# Copy_of_STM32_F407_SchDoc.net
KiCad netlist of a schematic drawn in Altium Designer
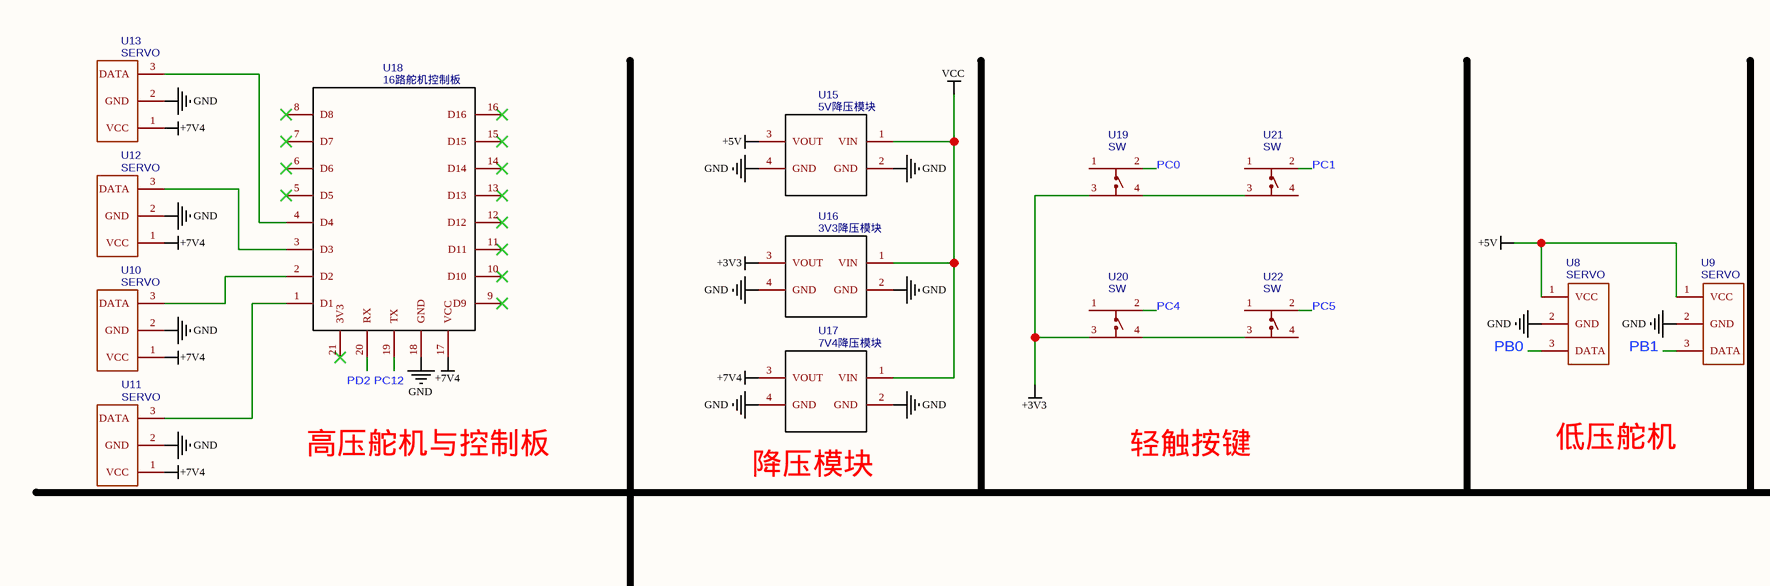
[diagram p0: Copy of STM32_F407.SchDoc.schdoc, top left]
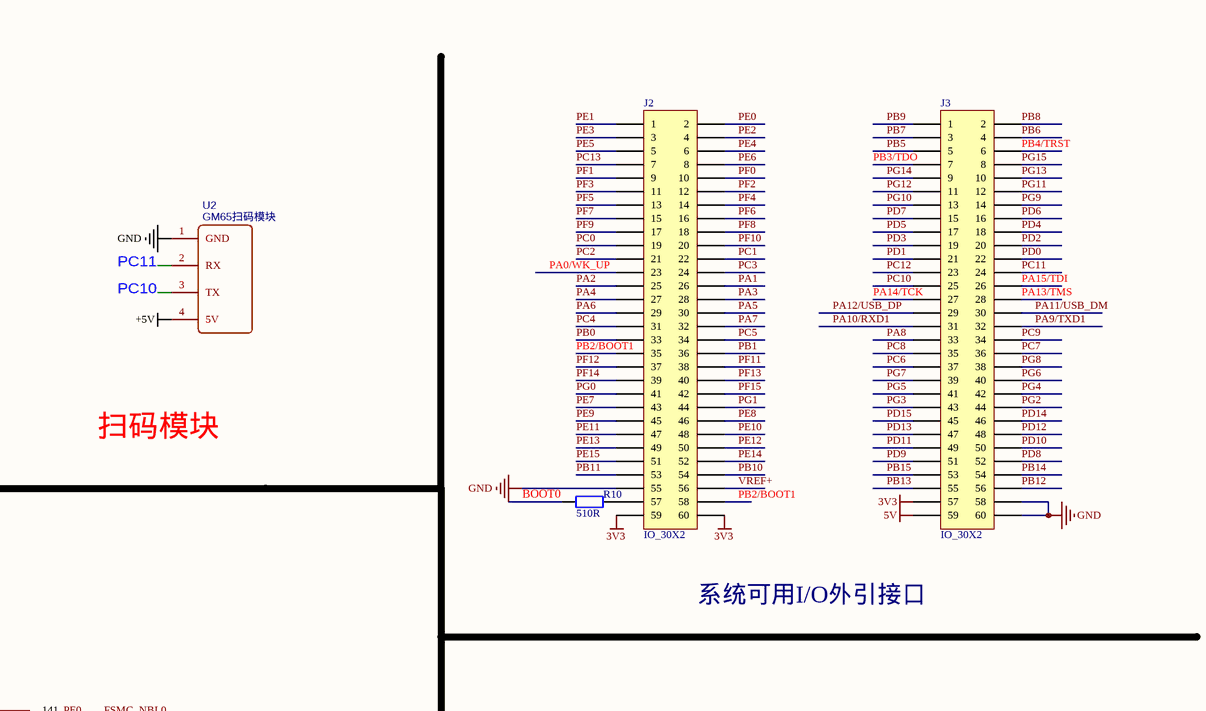
[diagram p1: Copy of STM32_F407.SchDoc.schdoc, top right]
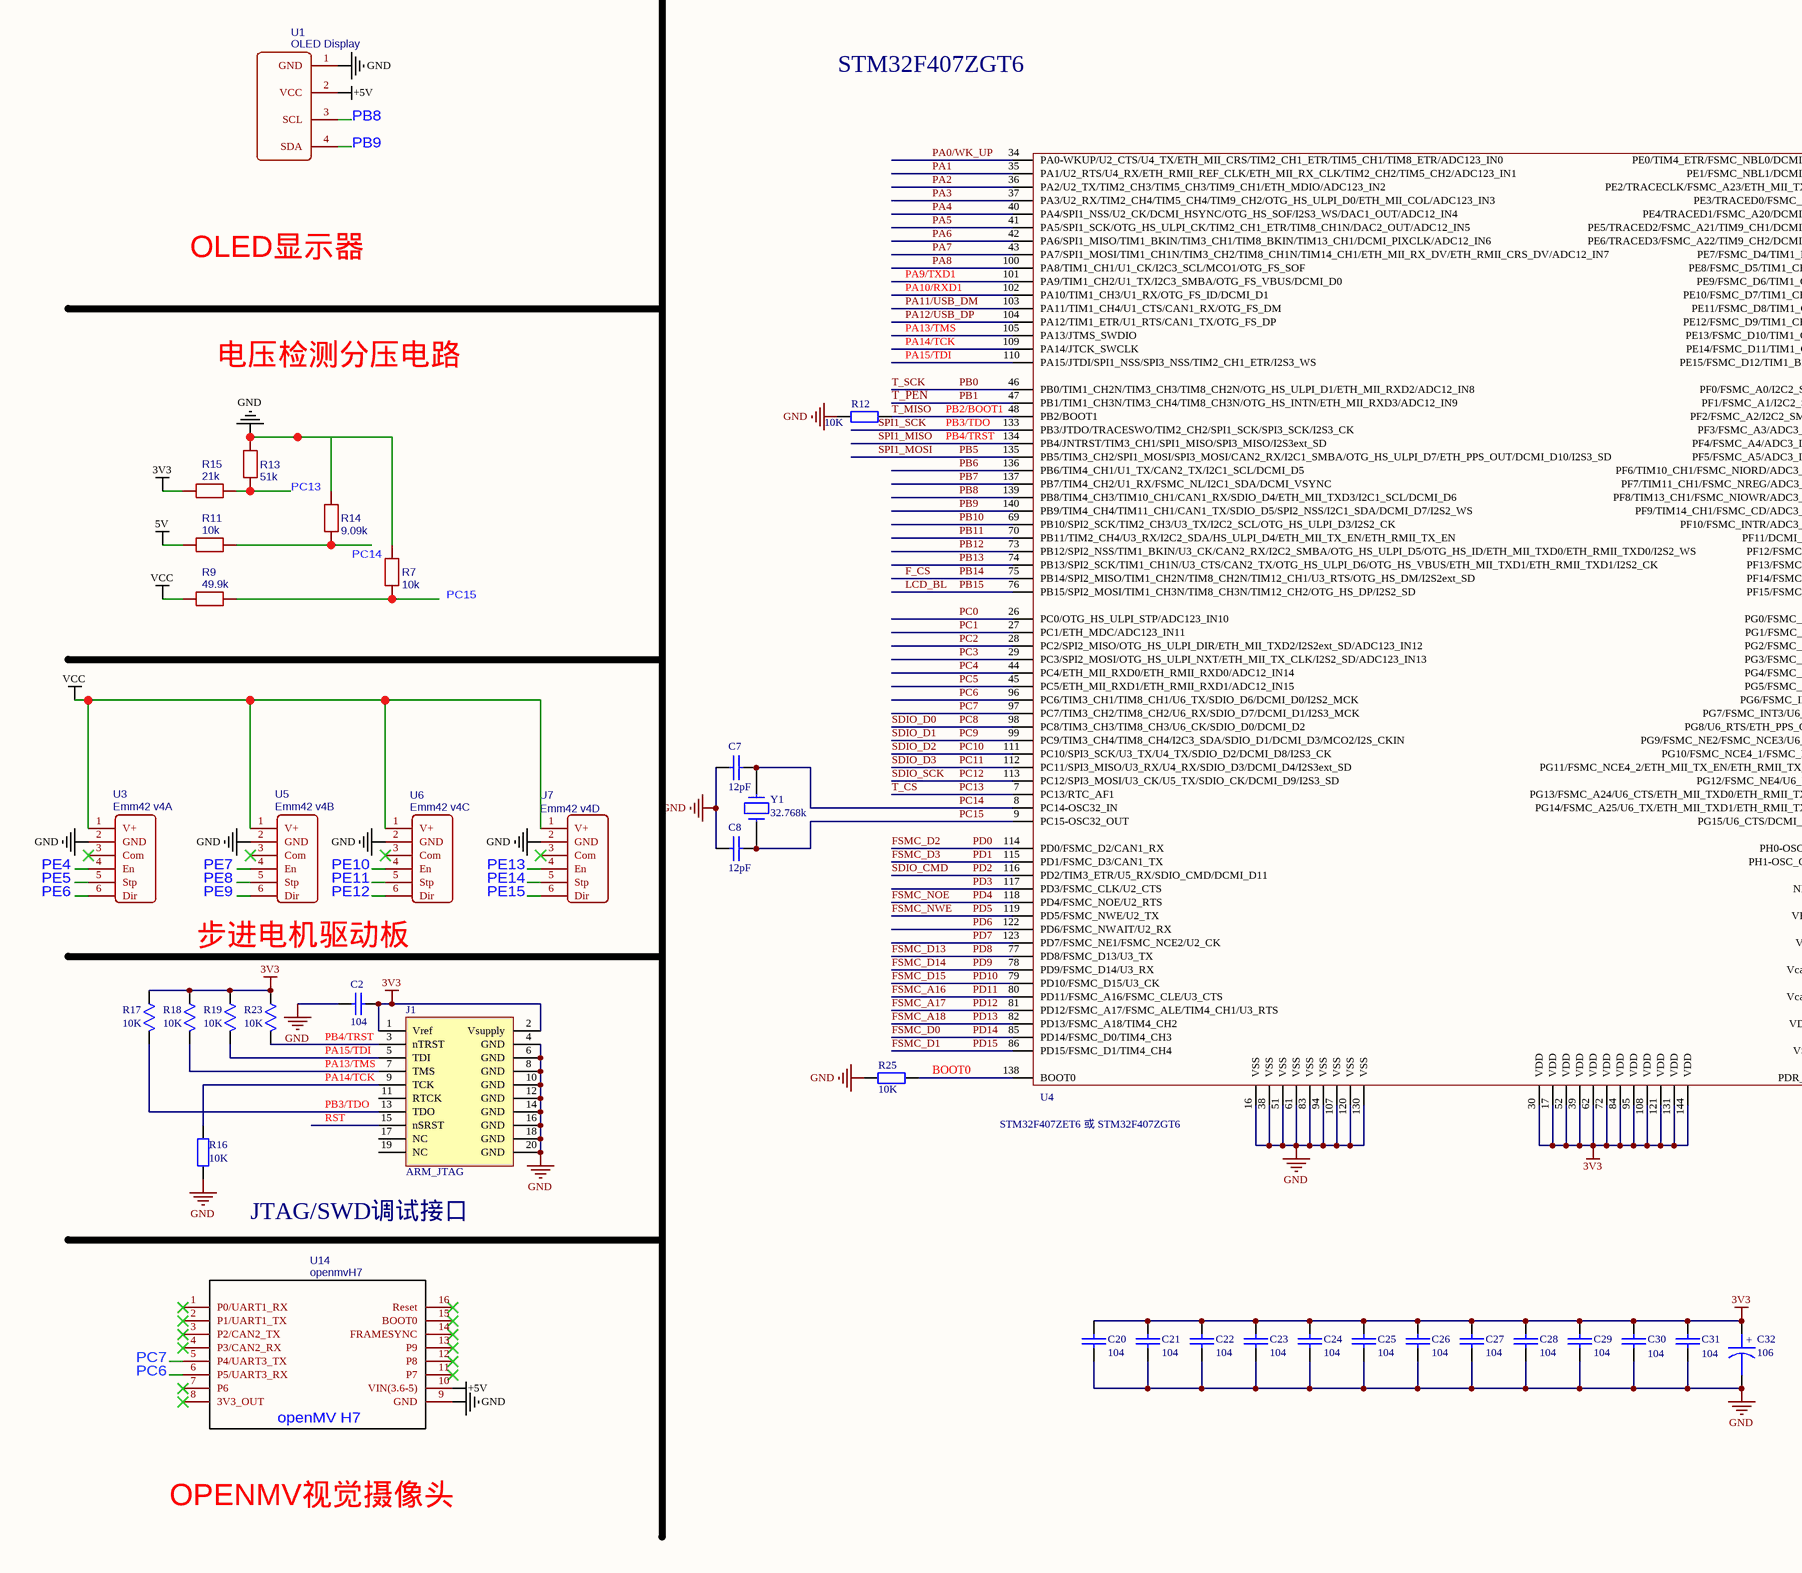
[diagram p2: Copy of STM32_F407.SchDoc.schdoc, bottom left]
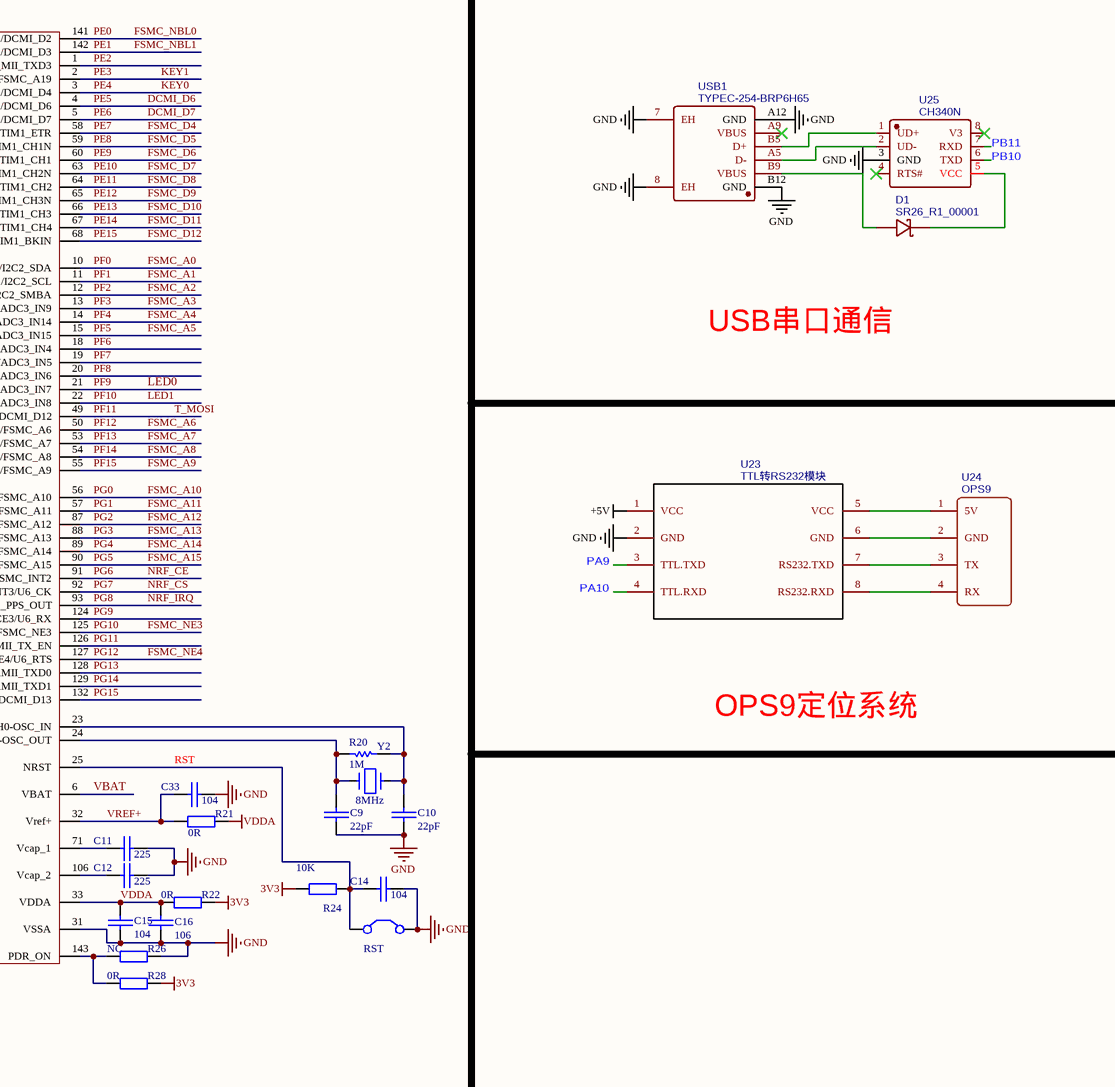
[diagram p3: Copy of STM32_F407.SchDoc.schdoc, bottom right]

(export (version "E")
  (design (tool "Eeschema 10.0.6"))
  (components
    (comp (ref "C2")
      (value "NO")
      (fields (field (name "PUBLISHER") "Altium Limited"))
      (libsource (lib "altium-import") (part "root_0_NO_"))
    )
    (comp (ref "C7") (value "12pF") (libsource (lib "altium-import") (part "root_1_12pF_")))
    (comp (ref "C8") (value "12pF") (libsource (lib "altium-import") (part "root_1_12pF_")))
    (comp (ref "C9") (value "22pF") (libsource (lib "altium-import") (part "root_0_22pF_")))
    (comp (ref "C10") (value "22pF") (libsource (lib "altium-import") (part "root_0_22pF_")))
    (comp (ref "C11") (value "225") (libsource (lib "altium-import") (part "root_1_225_")))
    (comp (ref "C12") (value "225") (libsource (lib "altium-import") (part "root_1_225_")))
    (comp (ref "C14") (value "104") (libsource (lib "") (part "root_1_104__1")))
    (comp (ref "C15") (value "104") (libsource (lib "altium-import") (part "root_2_104_")))
    (comp (ref "C16") (value "106") (libsource (lib "altium-import") (part "root_2_106_")))
    (comp (ref "C20") (value "104") (libsource (lib "altium-import") (part "root_0_104_")))
    (comp (ref "C21") (value "104") (libsource (lib "altium-import") (part "root_0_104_")))
    (comp (ref "C22") (value "104") (libsource (lib "altium-import") (part "root_0_104_")))
    (comp (ref "C23") (value "104") (libsource (lib "altium-import") (part "root_0_104_")))
    (comp (ref "C24") (value "104") (libsource (lib "altium-import") (part "root_0_104_")))
    (comp (ref "C25") (value "104") (libsource (lib "altium-import") (part "root_0_104_")))
    (comp (ref "C26") (value "104") (libsource (lib "altium-import") (part "root_0_104_")))
    (comp (ref "C27") (value "104") (libsource (lib "altium-import") (part "root_0_104_")))
    (comp (ref "C28") (value "104") (libsource (lib "altium-import") (part "root_0_104_")))
    (comp (ref "C29") (value "104") (libsource (lib "altium-import") (part "root_0_104_")))
    (comp (ref "C30") (value "104") (libsource (lib "altium-import") (part "root_0_104_")))
    (comp (ref "C31") (value "104") (libsource (lib "altium-import") (part "root_0_104_")))
    (comp (ref "C32") (value "106") (libsource (lib "altium-import") (part "root_0_106_")))
    (comp (ref "C33") (value "104") (libsource (lib "altium-import") (part "root_1_104_")))
    (comp (ref "D1")
      (value "SR26_R1_00001")
      (fields (field (name "MANUFACTURER") "PANJIT(强茂)") (field (name "CONTRIBUTOR") "LCSC"))
      (libsource (lib "altium-import") (part "root_2_SR26_R1_00001_"))
    )
    (comp (ref "J1") (value "ARM_JTAG") (libsource (lib "altium-import") (part "root_0_ARM_JTAG_")))
    (comp (ref "J2")
      (value "IO_30X2")
      (fields (field (name "PUBLISHER") "Altium Limited"))
      (libsource (lib "altium-import") (part "root_0_IO_30X2_"))
    )
    (comp (ref "J3")
      (value "IO_30X2")
      (fields (field (name "PUBLISHER") "Altium Limited"))
      (libsource (lib "altium-import") (part "root_0_IO_30X2_"))
    )
    (comp (ref "R7")
      (value "10k")
      (fields (field (name "CONTRIBUTOR") "LCEDA_Lib"))
      (libsource (lib "altium-import") (part "root_1_10k_"))
    )
    (comp (ref "R9")
      (value "49.9k")
      (fields (field (name "CONTRIBUTOR") "LCEDA_Lib"))
      (libsource (lib "altium-import") (part "root_0_49.9k_"))
    )
    (comp (ref "R10") (value "510R") (libsource (lib "altium-import") (part "root_2_510R_")))
    (comp (ref "R11")
      (value "10k")
      (fields (field (name "CONTRIBUTOR") "LCEDA_Lib"))
      (libsource (lib "altium-import") (part "root_0_10k_"))
    )
    (comp (ref "R12") (value "10K") (libsource (lib "altium-import") (part "root_2_10K_")))
    (comp (ref "R13")
      (value "51k")
      (fields (field (name "CONTRIBUTOR") "LCEDA_Lib"))
      (libsource (lib "altium-import") (part "root_1_51k_"))
    )
    (comp (ref "R14")
      (value "9.09k")
      (fields (field (name "CONTRIBUTOR") "LCEDA_Lib"))
      (libsource (lib "altium-import") (part "root_1_9.09k_"))
    )
    (comp (ref "R15")
      (value "21k")
      (fields (field (name "CONTRIBUTOR") "LCEDA_Lib"))
      (libsource (lib "altium-import") (part "root_0_21k_"))
    )
    (comp (ref "R16") (value "10K") (libsource (lib "altium-import") (part "root_1_10K_")))
    (comp (ref "R17") (value "10K") (libsource (lib "altium-import") (part "root_3_10K_")))
    (comp (ref "R18") (value "10K") (libsource (lib "altium-import") (part "root_3_10K_")))
    (comp (ref "R19") (value "10K") (libsource (lib "altium-import") (part "root_3_10K_")))
    (comp (ref "R20") (value "1M") (libsource (lib "altium-import") (part "root_0_1M_")))
    (comp (ref "R21") (value "0R") (libsource (lib "altium-import") (part "root_0_0R_")))
    (comp (ref "R22") (value "0R") (libsource (lib "altium-import") (part "root_0_0R_")))
    (comp (ref "R23") (value "10K") (libsource (lib "altium-import") (part "root_3_10K_")))
    (comp (ref "R24") (value "10K") (libsource (lib "altium-import") (part "root_2_10K_")))
    (comp (ref "R25") (value "10K") (libsource (lib "altium-import") (part "root_0_10K_")))
    (comp (ref "R26") (value "NC") (libsource (lib "altium-import") (part "root_0_NC_")))
    (comp (ref "R28") (value "0R") (libsource (lib "altium-import") (part "root_0_0R_")))
    (comp (ref "RST")
      (value "Key")
      (fields (field (name "PUBLISHER") "Altium Limited"))
      (libsource (lib "altium-import") (part "root_0_Key_"))
    )
    (comp (ref "U1")
      (value "OLED Display")
      (fields (field (name "CONTRIBUTOR") "mac149"))
      (libsource (lib "altium-import") (part "root_0_OLED Display_"))
    )
    (comp (ref "U2")
      (value "GM65扫码模块")
      (fields (field (name "CONTRIBUTOR") "mac149"))
      (libsource (lib "altium-import") (part "root_0_GM65扫码模块_"))
    )
    (comp (ref "U3")
      (value "Emm42 v4A")
      (fields (field (name "CONTRIBUTOR") "mac149"))
      (libsource (lib "altium-import") (part "root_0_Emm42 v4A_"))
    )
    (comp (ref "U4")
      (value "STM32F407ZET6 或 STM32F407ZGT6")
      (libsource (lib "altium-import") (part "root_0_STM32F407ZET6 或 STM32F407ZGT6_"))
    )
    (comp (ref "U5")
      (value "Emm42 v4B")
      (fields (field (name "CONTRIBUTOR") "mac149"))
      (libsource (lib "altium-import") (part "root_0_Emm42 v4B_"))
    )
    (comp (ref "U6")
      (value "Emm42 v4C")
      (fields (field (name "CONTRIBUTOR") "mac149"))
      (libsource (lib "altium-import") (part "root_0_Emm42 v4C_"))
    )
    (comp (ref "U7")
      (value "Emm42 v4D")
      (fields (field (name "CONTRIBUTOR") "mac149"))
      (libsource (lib "altium-import") (part "root_0_Emm42 v4D_"))
    )
    (comp (ref "U8")
      (value "SERVO")
      (fields (field (name "CONTRIBUTOR") "mac149"))
      (libsource (lib "altium-import") (part "root_0_SERVO_"))
    )
    (comp (ref "U9")
      (value "SERVO")
      (fields (field (name "CONTRIBUTOR") "mac149"))
      (libsource (lib "altium-import") (part "root_0_SERVO_"))
    )
    (comp (ref "U10")
      (value "SERVO")
      (fields (field (name "CONTRIBUTOR") "mac149"))
      (libsource (lib "altium-import") (part "root_2_SERVO_"))
    )
    (comp (ref "U11")
      (value "SERVO")
      (fields (field (name "CONTRIBUTOR") "mac149"))
      (libsource (lib "altium-import") (part "root_2_SERVO_"))
    )
    (comp (ref "U12")
      (value "SERVO")
      (fields (field (name "CONTRIBUTOR") "mac149"))
      (libsource (lib "altium-import") (part "root_2_SERVO_"))
    )
    (comp (ref "U13")
      (value "SERVO")
      (fields (field (name "CONTRIBUTOR") "mac149"))
      (libsource (lib "altium-import") (part "root_2_SERVO_"))
    )
    (comp (ref "U14")
      (value "openmvH7")
      (fields (field (name "CONTRIBUTOR") "xinb"))
      (libsource (lib "altium-import") (part "root_0_openmvH7_"))
    )
    (comp (ref "U15")
      (value "5V降压模块")
      (fields (field (name "CONTRIBUTOR") "mac149"))
      (libsource (lib "altium-import") (part "root_0_5V降压模块_"))
    )
    (comp (ref "U16")
      (value "3V3降压模块")
      (fields (field (name "CONTRIBUTOR") "mac149"))
      (libsource (lib "altium-import") (part "root_0_3V3降压模块_"))
    )
    (comp (ref "U17")
      (value "7V4降压模块")
      (fields (field (name "CONTRIBUTOR") "mac149"))
      (libsource (lib "altium-import") (part "root_0_7V4降压模块_"))
    )
    (comp (ref "U18")
      (value "16路舵机控制板")
      (fields (field (name "CONTRIBUTOR") "mac149"))
      (libsource (lib "altium-import") (part "root_2_16路舵机控制板_"))
    )
    (comp (ref "U19")
      (value "SW")
      (fields
        (field (name "MANUFACTURER") "DEALON(德艺隆)")
        (field (name "MANUFACTURER PART") "TD-1806SR-5.5H-250")
        (field (name "CONTRIBUTOR") "lcsc")
      )
      (libsource (lib "altium-import") (part "root_0_SW_"))
    )
    (comp (ref "U20")
      (value "SW")
      (fields
        (field (name "MANUFACTURER") "DEALON(德艺隆)")
        (field (name "MANUFACTURER PART") "TD-1806SR-5.5H-250")
        (field (name "CONTRIBUTOR") "lcsc")
      )
      (libsource (lib "altium-import") (part "root_0_SW_"))
    )
    (comp (ref "U21")
      (value "SW")
      (fields
        (field (name "MANUFACTURER") "DEALON(德艺隆)")
        (field (name "MANUFACTURER PART") "TD-1806SR-5.5H-250")
        (field (name "CONTRIBUTOR") "lcsc")
      )
      (libsource (lib "altium-import") (part "root_0_SW_"))
    )
    (comp (ref "U22")
      (value "SW")
      (fields
        (field (name "MANUFACTURER") "DEALON(德艺隆)")
        (field (name "MANUFACTURER PART") "TD-1806SR-5.5H-250")
        (field (name "CONTRIBUTOR") "lcsc")
      )
      (libsource (lib "altium-import") (part "root_0_SW_"))
    )
    (comp (ref "U23")
      (value "TTL转RS232模块")
      (fields (field (name "CONTRIBUTOR") "mac149"))
      (libsource (lib "altium-import") (part "root_0_TTL转RS232模块_"))
    )
    (comp (ref "U24")
      (value "OPS9")
      (fields (field (name "CONTRIBUTOR") "mac149"))
      (libsource (lib "altium-import") (part "root_0_OPS9_"))
    )
    (comp (ref "U25")
      (value "CH340N")
      (fields (field (name "MANUFACTURER") "WCH(南京沁恒)") (field (name "CONTRIBUTOR") "LCSC"))
      (libsource (lib "altium-import") (part "root_0_CH340N_"))
    )
    (comp (ref "USB1")
      (value "TYPEC-254-BRP6H65")
      (fields (field (name "MANUFACTURER") "XUNPU(讯普)") (field (name "CONTRIBUTOR") "LCSC"))
      (libsource (lib "altium-import") (part "root_2_TYPEC-254-BRP6H65_"))
    )
    (comp (ref "Y1") (value "8MHz") (libsource (lib "altium-import") (part "root_1_8MHz_")))
    (comp (ref "Y2") (value "8MHz") (libsource (lib "altium-import") (part "root_0_8MHz_")))
  )
  (nets
    (net (code "1") (name "+3V3") (class "Default")
      (node (ref "U16") (pin "3") (pinfunction "VOUT_3") (pintype "passive"))
      (node (ref "U19") (pin "3") (pinfunction "C_3") (pintype "passive"))
      (node (ref "U20") (pin "3") (pinfunction "C_3") (pintype "passive"))
    )
    (net (code "2") (name "+5V") (class "Default")
      (node (ref "U1") (pin "2") (pinfunction "VCC_2") (pintype "passive"))
      (node (ref "U14") (pin "10") (pinfunction "VIN(3.6-5)_10") (pintype "passive"))
      (node (ref "U15") (pin "3") (pinfunction "VOUT_3") (pintype "passive"))
      (node (ref "U2") (pin "4") (pinfunction "5V_4") (pintype "passive"))
      (node (ref "U23") (pin "1") (pinfunction "VCC_1") (pintype "passive"))
      (node (ref "U8") (pin "1") (pinfunction "VCC_1") (pintype "passive"))
      (node (ref "U9") (pin "1") (pinfunction "VCC_1") (pintype "passive"))
    )
    (net (code "3") (name "+7V4") (class "Default")
      (node (ref "U10") (pin "1") (pinfunction "VCC_1") (pintype "passive"))
      (node (ref "U11") (pin "1") (pinfunction "VCC_1") (pintype "passive"))
      (node (ref "U12") (pin "1") (pinfunction "VCC_1") (pintype "passive"))
      (node (ref "U13") (pin "1") (pinfunction "VCC_1") (pintype "passive"))
      (node (ref "U17") (pin "3") (pinfunction "VOUT_3") (pintype "passive"))
      (node (ref "U18") (pin "17") (pinfunction "VCC_17") (pintype "passive"))
    )
    (net (code "4") (name "/BOOT0") (class "Default")
      (node (ref "R10") (pin "2") (pinfunction "2_2") (pintype "passive"))
      (node (ref "R25") (pin "1") (pinfunction "1_1") (pintype "passive"))
      (node (ref "U4") (pin "138") (pinfunction "BOOT0_138") (pintype "passive"))
    )
    (net (code "5") (name "/DCMI_D6") (class "Default")
      (node (ref "J2") (pin "5") (pinfunction "5_5") (pintype "passive"))
      (node (ref "U4") (pin "4") (pinfunction "PE5/TRACED2/FSMC_A21/TIM9_CH1/DCMI_D6_4") (pintype "passive"))
    )
    (net (code "6") (name "/DCMI_D7") (class "Default")
      (node (ref "J2") (pin "8") (pinfunction "8_8") (pintype "passive"))
      (node (ref "U4") (pin "5") (pinfunction "PE6/TRACED3/FSMC_A22/TIM9_CH2/DCMI_D7_5") (pintype "passive"))
    )
    (net (code "7") (name "/FSMC_A0") (class "Default")
      (node (ref "J2") (pin "10") (pinfunction "10_10") (pintype "passive"))
      (node (ref "U4") (pin "10") (pinfunction "PF0/FSMC_A0/I2C2_SDA_10") (pintype "passive"))
    )
    (net (code "8") (name "/FSMC_A1") (class "Default")
      (node (ref "J2") (pin "9") (pinfunction "9_9") (pintype "passive"))
      (node (ref "U4") (pin "11") (pinfunction "PF1/FSMC_A1/I2C2_SCL_11") (pintype "passive"))
    )
    (net (code "9") (name "/FSMC_A2") (class "Default")
      (node (ref "J2") (pin "12") (pinfunction "12_12") (pintype "passive"))
      (node (ref "U4") (pin "12") (pinfunction "PF2/FSMC_A2/I2C2_SMBA_12") (pintype "passive"))
    )
    (net (code "10") (name "/FSMC_A3") (class "Default")
      (node (ref "J2") (pin "11") (pinfunction "11_11") (pintype "passive"))
      (node (ref "U4") (pin "13") (pinfunction "PF3/FSMC_A3/ADC3_IN9_13") (pintype "passive"))
    )
    (net (code "11") (name "/FSMC_A4") (class "Default")
      (node (ref "J2") (pin "14") (pinfunction "14_14") (pintype "passive"))
      (node (ref "U4") (pin "14") (pinfunction "PF4/FSMC_A4/ADC3_IN14_14") (pintype "passive"))
    )
    (net (code "12") (name "/FSMC_A5") (class "Default")
      (node (ref "J2") (pin "13") (pinfunction "13_13") (pintype "passive"))
      (node (ref "U4") (pin "15") (pinfunction "PF5/FSMC_A5/ADC3_IN15_15") (pintype "passive"))
    )
    (net (code "13") (name "/FSMC_A6") (class "Default")
      (node (ref "J2") (pin "37") (pinfunction "37_37") (pintype "passive"))
      (node (ref "U4") (pin "50") (pinfunction "PF12/FSMC_A6_50") (pintype "passive"))
    )
    (net (code "14") (name "/FSMC_A7") (class "Default")
      (node (ref "J2") (pin "40") (pinfunction "40_40") (pintype "passive"))
      (node (ref "U4") (pin "53") (pinfunction "PF13/FSMC_A7_53") (pintype "passive"))
    )
    (net (code "15") (name "/FSMC_A8") (class "Default")
      (node (ref "J2") (pin "39") (pinfunction "39_39") (pintype "passive"))
      (node (ref "U4") (pin "54") (pinfunction "PF14/FSMC_A8_54") (pintype "passive"))
    )
    (net (code "16") (name "/FSMC_A9") (class "Default")
      (node (ref "J2") (pin "42") (pinfunction "42_42") (pintype "passive"))
      (node (ref "U4") (pin "55") (pinfunction "PF15/FSMC_A9_55") (pintype "passive"))
    )
    (net (code "17") (name "/FSMC_A10") (class "Default")
      (node (ref "J2") (pin "41") (pinfunction "41_41") (pintype "passive"))
      (node (ref "U4") (pin "56") (pinfunction "PG0/FSMC_A10_56") (pintype "passive"))
    )
    (net (code "18") (name "/FSMC_A11") (class "Default")
      (node (ref "J2") (pin "44") (pinfunction "44_44") (pintype "passive"))
      (node (ref "U4") (pin "57") (pinfunction "PG1/FSMC_A11_57") (pintype "passive"))
    )
    (net (code "19") (name "/FSMC_A12") (class "Default")
      (node (ref "J3") (pin "44") (pinfunction "44_44") (pintype "passive"))
      (node (ref "U4") (pin "87") (pinfunction "PG2/FSMC_A12_87") (pintype "passive"))
    )
    (net (code "20") (name "/FSMC_A13") (class "Default")
      (node (ref "J3") (pin "43") (pinfunction "43_43") (pintype "passive"))
      (node (ref "U4") (pin "88") (pinfunction "PG3/FSMC_A13_88") (pintype "passive"))
    )
    (net (code "21") (name "/FSMC_A14") (class "Default")
      (node (ref "J3") (pin "42") (pinfunction "42_42") (pintype "passive"))
      (node (ref "U4") (pin "89") (pinfunction "PG4/FSMC_A14_89") (pintype "passive"))
    )
    (net (code "22") (name "/FSMC_A15") (class "Default")
      (node (ref "J3") (pin "41") (pinfunction "41_41") (pintype "passive"))
      (node (ref "U4") (pin "90") (pinfunction "PG5/FSMC_A15_90") (pintype "passive"))
    )
    (net (code "23") (name "/FSMC_A16") (class "Default")
      (node (ref "J3") (pin "49") (pinfunction "49_49") (pintype "passive"))
      (node (ref "U4") (pin "80") (pinfunction "PD11/FSMC_A16/FSMC_CLE/U3_CTS_80") (pintype "passive"))
    )
    (net (code "24") (name "/FSMC_A17") (class "Default")
      (node (ref "J3") (pin "48") (pinfunction "48_48") (pintype "passive"))
      (node (ref "U4") (pin "81") (pinfunction "PD12/FSMC_A17/FSMC_ALE/TIM4_CH1/U3_RTS_81") (pintype "passive"))
    )
    (net (code "25") (name "/FSMC_A18") (class "Default")
      (node (ref "J3") (pin "47") (pinfunction "47_47") (pintype "passive"))
      (node (ref "U4") (pin "82") (pinfunction "PD13/FSMC_A18/TIM4_CH2_82") (pintype "passive"))
    )
    (net (code "26") (name "/FSMC_D0") (class "Default")
      (node (ref "J3") (pin "46") (pinfunction "46_46") (pintype "passive"))
      (node (ref "U4") (pin "85") (pinfunction "PD14/FSMC_D0/TIM4_CH3_85") (pintype "passive"))
    )
    (net (code "27") (name "/FSMC_D1") (class "Default")
      (node (ref "J3") (pin "45") (pinfunction "45_45") (pintype "passive"))
      (node (ref "U4") (pin "86") (pinfunction "PD15/FSMC_D1/TIM4_CH4_86") (pintype "passive"))
    )
    (net (code "28") (name "/FSMC_D2") (class "Default")
      (node (ref "J3") (pin "22") (pinfunction "22_22") (pintype "passive"))
      (node (ref "U4") (pin "114") (pinfunction "PD0/FSMC_D2/CAN1_RX_114") (pintype "passive"))
    )
    (net (code "29") (name "/FSMC_D3") (class "Default")
      (node (ref "J3") (pin "21") (pinfunction "21_21") (pintype "passive"))
      (node (ref "U4") (pin "115") (pinfunction "PD1/FSMC_D3/CAN1_TX_115") (pintype "passive"))
    )
    (net (code "30") (name "/FSMC_D4") (class "Default")
      (node (ref "J2") (pin "43") (pinfunction "43_43") (pintype "passive"))
      (node (ref "U4") (pin "58") (pinfunction "PE7/FSMC_D4/TIM1_ETR_58") (pintype "passive"))
    )
    (net (code "31") (name "/FSMC_D5") (class "Default")
      (node (ref "J2") (pin "46") (pinfunction "46_46") (pintype "passive"))
      (node (ref "U4") (pin "59") (pinfunction "PE8/FSMC_D5/TIM1_CH1N_59") (pintype "passive"))
    )
    (net (code "32") (name "/FSMC_D6") (class "Default")
      (node (ref "J2") (pin "45") (pinfunction "45_45") (pintype "passive"))
      (node (ref "U4") (pin "60") (pinfunction "PE9/FSMC_D6/TIM1_CH1_60") (pintype "passive"))
    )
    (net (code "33") (name "/FSMC_D7") (class "Default")
      (node (ref "J2") (pin "48") (pinfunction "48_48") (pintype "passive"))
      (node (ref "U4") (pin "63") (pinfunction "PE10/FSMC_D7/TIM1_CH2N_63") (pintype "passive"))
    )
    (net (code "34") (name "/FSMC_D8") (class "Default")
      (node (ref "J2") (pin "47") (pinfunction "47_47") (pintype "passive"))
      (node (ref "U4") (pin "64") (pinfunction "PE11/FSMC_D8/TIM1_CH2_64") (pintype "passive"))
    )
    (net (code "35") (name "/FSMC_D9") (class "Default")
      (node (ref "J2") (pin "50") (pinfunction "50_50") (pintype "passive"))
      (node (ref "U4") (pin "65") (pinfunction "PE12/FSMC_D9/TIM1_CH3N_65") (pintype "passive"))
    )
    (net (code "36") (name "/FSMC_D10") (class "Default")
      (node (ref "J2") (pin "49") (pinfunction "49_49") (pintype "passive"))
      (node (ref "U4") (pin "66") (pinfunction "PE13/FSMC_D10/TIM1_CH3_66") (pintype "passive"))
    )
    (net (code "37") (name "/FSMC_D11") (class "Default")
      (node (ref "J2") (pin "52") (pinfunction "52_52") (pintype "passive"))
      (node (ref "U4") (pin "67") (pinfunction "PE14/FSMC_D11/TIM1_CH4_67") (pintype "passive"))
    )
    (net (code "38") (name "/FSMC_D12") (class "Default")
      (node (ref "J2") (pin "51") (pinfunction "51_51") (pintype "passive"))
      (node (ref "U4") (pin "68") (pinfunction "PE15/FSMC_D12/TIM1_BKIN_68") (pintype "passive"))
    )
    (net (code "39") (name "/FSMC_D13") (class "Default")
      (node (ref "J3") (pin "52") (pinfunction "52_52") (pintype "passive"))
      (node (ref "U4") (pin "77") (pinfunction "PD8/FSMC_D13/U3_TX_77") (pintype "passive"))
    )
    (net (code "40") (name "/FSMC_D14") (class "Default")
      (node (ref "J3") (pin "51") (pinfunction "51_51") (pintype "passive"))
      (node (ref "U4") (pin "78") (pinfunction "PD9/FSMC_D14/U3_RX_78") (pintype "passive"))
    )
    (net (code "41") (name "/FSMC_D15") (class "Default")
      (node (ref "J3") (pin "50") (pinfunction "50_50") (pintype "passive"))
      (node (ref "U4") (pin "79") (pinfunction "PD10/FSMC_D15/U3_CK_79") (pintype "passive"))
    )
    (net (code "42") (name "/FSMC_NBL0") (class "Default")
      (node (ref "J2") (pin "2") (pinfunction "2_2") (pintype "passive"))
      (node (ref "U4") (pin "141") (pinfunction "PE0/TIM4_ETR/FSMC_NBL0/DCMI_D2_141") (pintype "passive"))
    )
    (net (code "43") (name "/FSMC_NBL1") (class "Default")
      (node (ref "J2") (pin "1") (pinfunction "1_1") (pintype "passive"))
      (node (ref "U4") (pin "142") (pinfunction "PE1/FSMC_NBL1/DCMI_D3_142") (pintype "passive"))
    )
    (net (code "44") (name "/FSMC_NE3") (class "Default")
      (node (ref "J3") (pin "13") (pinfunction "13_13") (pintype "passive"))
      (node (ref "U4") (pin "125") (pinfunction "PG10/FSMC_NCE4_1/FSMC_NE3_125") (pintype "passive"))
    )
    (net (code "45") (name "/FSMC_NE4") (class "Default")
      (node (ref "J3") (pin "11") (pinfunction "11_11") (pintype "passive"))
      (node (ref "U4") (pin "127") (pinfunction "PG12/FSMC_NE4/U6_RTS_127") (pintype "passive"))
    )
    (net (code "46") (name "/FSMC_NOE") (class "Default")
      (node (ref "J3") (pin "18") (pinfunction "18_18") (pintype "passive"))
      (node (ref "U4") (pin "118") (pinfunction "PD4/FSMC_NOE/U2_RTS_118") (pintype "passive"))
    )
    (net (code "47") (name "/FSMC_NWE") (class "Default")
      (node (ref "J3") (pin "17") (pinfunction "17_17") (pintype "passive"))
      (node (ref "U4") (pin "119") (pinfunction "PD5/FSMC_NWE/U2_TX_119") (pintype "passive"))
    )
    (net (code "48") (name "/F_CS") (class "Default")
      (node (ref "J3") (pin "54") (pinfunction "54_54") (pintype "passive"))
      (node (ref "U4") (pin "75") (pinfunction "PB14/SPI2_MISO/TIM1_CH2N/TIM8_CH2N/TIM12_CH1/U3_RTS/OTG_HS_DM/I2S2ext_SD_75") (pintype "passive"))
    )
    (net (code "49") (name "/KEY0") (class "Default")
      (node (ref "J2") (pin "6") (pinfunction "6_6") (pintype "passive"))
      (node (ref "U4") (pin "3") (pinfunction "PE4/TRACED1/FSMC_A20/DCMI_D4_3") (pintype "passive"))
    )
    (net (code "50") (name "/KEY1") (class "Default")
      (node (ref "J2") (pin "3") (pinfunction "3_3") (pintype "passive"))
      (node (ref "U4") (pin "2") (pinfunction "PE3/TRACED0/FSMC_A19_2") (pintype "passive"))
    )
    (net (code "51") (name "/LCD_BL") (class "Default")
      (node (ref "J3") (pin "53") (pinfunction "53_53") (pintype "passive"))
      (node (ref "U4") (pin "76") (pinfunction "PB15/SPI2_MOSI/TIM1_CH3N/TIM8_CH3N/TIM12_CH2/OTG_HS_DP/I2S2_SD_76") (pintype "passive"))
    )
    (net (code "52") (name "/LED0") (class "Default")
      (node (ref "J2") (pin "17") (pinfunction "17_17") (pintype "passive"))
      (node (ref "U4") (pin "21") (pinfunction "PF9/TIM14_CH1/FSMC_CD/ADC3_IN7_21") (pintype "passive"))
    )
    (net (code "53") (name "/LED1") (class "Default")
      (node (ref "J2") (pin "20") (pinfunction "20_20") (pintype "passive"))
      (node (ref "U4") (pin "22") (pinfunction "PF10/FSMC_INTR/ADC3_IN8_22") (pintype "passive"))
    )
    (net (code "54") (name "/NRF_CE") (class "Default")
      (node (ref "J3") (pin "40") (pinfunction "40_40") (pintype "passive"))
      (node (ref "U4") (pin "91") (pinfunction "PG6/FSMC_INT2_91") (pintype "passive"))
    )
    (net (code "55") (name "/NRF_CS") (class "Default")
      (node (ref "J3") (pin "39") (pinfunction "39_39") (pintype "passive"))
      (node (ref "U4") (pin "92") (pinfunction "PG7/FSMC_INT3/U6_CK_92") (pintype "passive"))
    )
    (net (code "56") (name "/NRF_IRQ") (class "Default")
      (node (ref "J3") (pin "38") (pinfunction "38_38") (pintype "passive"))
      (node (ref "U4") (pin "93") (pinfunction "PG8/U6_RTS/ETH_PPS_OUT_93") (pintype "passive"))
    )
    (net (code "57") (name "/PA0{slash}WK_UP") (class "Default")
      (node (ref "J2") (pin "23") (pinfunction "23_23") (pintype "passive"))
      (node (ref "U4") (pin "34") (pinfunction "PA0-WKUP/U2_CTS/U4_TX/ETH_MII_CRS/TIM2_CH1_ETR/TIM5_CH1/TIM8_ETR/ADC123_IN0_34") (pintype "passive"))
    )
    (net (code "58") (name "/PA1") (class "Default")
      (node (ref "J2") (pin "26") (pinfunction "26_26") (pintype "passive"))
      (node (ref "U4") (pin "35") (pinfunction "PA1/U2_RTS/U4_RX/ETH_RMII_REF_CLK/ETH_MII_RX_CLK/TIM2_CH2/TIM5_CH2/ADC123_IN1_35") (pintype "passive"))
    )
    (net (code "59") (name "/PA2") (class "Default")
      (node (ref "J2") (pin "25") (pinfunction "25_25") (pintype "passive"))
      (node (ref "U4") (pin "36") (pinfunction "PA2/U2_TX/TIM2_CH3/TIM5_CH3/TIM9_CH1/ETH_MDIO/ADC123_IN2_36") (pintype "passive"))
    )
    (net (code "60") (name "/PA3") (class "Default")
      (node (ref "J2") (pin "28") (pinfunction "28_28") (pintype "passive"))
      (node (ref "U4") (pin "37") (pinfunction "PA3/U2_RX/TIM2_CH4/TIM5_CH4/TIM9_CH2/OTG_HS_ULPI_D0/ETH_MII_COL/ADC123_IN3_37") (pintype "passive"))
    )
    (net (code "61") (name "/PA4") (class "Default")
      (node (ref "J2") (pin "27") (pinfunction "27_27") (pintype "passive"))
      (node (ref "U4") (pin "40") (pinfunction "PA4/SPI1_NSS/U2_CK/DCMI_HSYNC/OTG_HS_SOF/I2S3_WS/DAC1_OUT/ADC12_IN4_40") (pintype "passive"))
    )
    (net (code "62") (name "/PA5") (class "Default")
      (node (ref "J2") (pin "30") (pinfunction "30_30") (pintype "passive"))
      (node (ref "U4") (pin "41") (pinfunction "PA5/SPI1_SCK/OTG_HS_ULPI_CK/TIM2_CH1_ETR/TIM8_CH1N/DAC2_OUT/ADC12_IN5_41") (pintype "passive"))
    )
    (net (code "63") (name "/PA6") (class "Default")
      (node (ref "J2") (pin "29") (pinfunction "29_29") (pintype "passive"))
      (node (ref "U4") (pin "42") (pinfunction "PA6/SPI1_MISO/TIM1_BKIN/TIM3_CH1/TIM8_BKIN/TIM13_CH1/DCMI_PIXCLK/ADC12_IN6_42") (pintype "passive"))
    )
    (net (code "64") (name "/PA7") (class "Default")
      (node (ref "J2") (pin "32") (pinfunction "32_32") (pintype "passive"))
      (node (ref "U4") (pin "43") (pinfunction "PA7/SPI1_MOSI/TIM1_CH1N/TIM3_CH2/TIM8_CH1N/TIM14_CH1/ETH_MII_RX_DV/ETH_RMII_CRS_DV/ADC12_IN7_43") (pintype "passive"))
    )
    (net (code "65") (name "/PA8") (class "Default")
      (node (ref "J3") (pin "33") (pinfunction "33_33") (pintype "passive"))
      (node (ref "U4") (pin "100") (pinfunction "PA8/TIM1_CH1/U1_CK/I2C3_SCL/MCO1/OTG_FS_SOF_100") (pintype "passive"))
    )
    (net (code "66") (name "/PA9{slash}TXD1") (class "Default")
      (node (ref "J3") (pin "32") (pinfunction "32_32") (pintype "passive"))
      (node (ref "U4") (pin "101") (pinfunction "PA9/TIM1_CH2/U1_TX/I2C3_SMBA/OTG_FS_VBUS/DCMI_D0_101") (pintype "passive"))
    )
    (net (code "67") (name "/PA10{slash}RXD1") (class "Default")
      (node (ref "J3") (pin "31") (pinfunction "31_31") (pintype "passive"))
      (node (ref "U4") (pin "102") (pinfunction "PA10/TIM1_CH3/U1_RX/OTG_FS_ID/DCMI_D1_102") (pintype "passive"))
    )
    (net (code "68") (name "/PA11{slash}USB_DM") (class "Default")
      (node (ref "J3") (pin "30") (pinfunction "30_30") (pintype "passive"))
      (node (ref "U4") (pin "103") (pinfunction "PA11/TIM1_CH4/U1_CTS/CAN1_RX/OTG_FS_DM_103") (pintype "passive"))
    )
    (net (code "69") (name "/PA12{slash}USB_DP") (class "Default")
      (node (ref "J3") (pin "29") (pinfunction "29_29") (pintype "passive"))
      (node (ref "U4") (pin "104") (pinfunction "PA12/TIM1_ETR/U1_RTS/CAN1_TX/OTG_FS_DP_104") (pintype "passive"))
    )
    (net (code "70") (name "/PA13{slash}TMS") (class "Default")
      (node (ref "J1") (pin "7") (pinfunction "TMS_7") (pintype "passive"))
      (node (ref "J3") (pin "28") (pinfunction "28_28") (pintype "passive"))
      (node (ref "R18") (pin "2") (pinfunction "2_2") (pintype "passive"))
      (node (ref "U4") (pin "105") (pinfunction "PA13/JTMS_SWDIO_105") (pintype "passive"))
    )
    (net (code "71") (name "/PA14{slash}TCK") (class "Default")
      (node (ref "J1") (pin "9") (pinfunction "TCK_9") (pintype "passive"))
      (node (ref "J3") (pin "27") (pinfunction "27_27") (pintype "passive"))
      (node (ref "R16") (pin "2") (pinfunction "2_2") (pintype "passive"))
      (node (ref "U4") (pin "109") (pinfunction "PA14/JTCK_SWCLK_109") (pintype "passive"))
    )
    (net (code "72") (name "/PA15{slash}TDI") (class "Default")
      (node (ref "J1") (pin "5") (pinfunction "TDI_5") (pintype "passive"))
      (node (ref "J3") (pin "26") (pinfunction "26_26") (pintype "passive"))
      (node (ref "R19") (pin "2") (pinfunction "2_2") (pintype "passive"))
      (node (ref "U4") (pin "110") (pinfunction "PA15/JTDI/SPI1_NSS/SPI3_NSS/TIM2_CH1_ETR/I2S3_WS_110") (pintype "passive"))
    )
    (net (code "73") (name "/PB0") (class "Default")
      (node (ref "J2") (pin "33") (pinfunction "33_33") (pintype "passive"))
      (node (ref "U4") (pin "46") (pinfunction "PB0/TIM1_CH2N/TIM3_CH3/TIM8_CH2N/OTG_HS_ULPI_D1/ETH_MII_RXD2/ADC12_IN8_46") (pintype "passive"))
    )
    (net (code "74") (name "/PB1") (class "Default")
      (node (ref "J2") (pin "36") (pinfunction "36_36") (pintype "passive"))
      (node (ref "U4") (pin "47") (pinfunction "PB1/TIM1_CH3N/TIM3_CH4/TIM8_CH3N/OTG_HS_INTN/ETH_MII_RXD3/ADC12_IN9_47") (pintype "passive"))
    )
    (net (code "75") (name "/PB2{slash}BOOT1") (class "Default")
      (node (ref "J2") (pin "35") (pinfunction "35_35") (pintype "passive"))
      (node (ref "J2") (pin "58") (pinfunction "58_58") (pintype "passive"))
      (node (ref "R12") (pin "1") (pinfunction "1_1") (pintype "passive"))
      (node (ref "U4") (pin "48") (pinfunction "PB2/BOOT1_48") (pintype "passive"))
    )
    (net (code "76") (name "/PB3{slash}TDO") (class "Default")
      (node (ref "J1") (pin "13") (pinfunction "TDO_13") (pintype "passive"))
      (node (ref "J3") (pin "7") (pinfunction "7_7") (pintype "passive"))
      (node (ref "R17") (pin "2") (pinfunction "2_2") (pintype "passive"))
      (node (ref "U4") (pin "133") (pinfunction "PB3/JTDO/TRACESWO/TIM2_CH2/SPI1_SCK/SPI3_SCK/I2S3_CK_133") (pintype "passive"))
    )
    (net (code "77") (name "/PB4{slash}TRST") (class "Default")
      (node (ref "J1") (pin "3") (pinfunction "nTRST_3") (pintype "passive"))
      (node (ref "J3") (pin "6") (pinfunction "6_6") (pintype "passive"))
      (node (ref "R23") (pin "2") (pinfunction "2_2") (pintype "passive"))
      (node (ref "U4") (pin "134") (pinfunction "PB4/JNTRST/TIM3_CH1/SPI1_MISO/SPI3_MISO/I2S3ext_SD_134") (pintype "passive"))
    )
    (net (code "78") (name "/PB5") (class "Default")
      (node (ref "J3") (pin "5") (pinfunction "5_5") (pintype "passive"))
      (node (ref "U4") (pin "135") (pinfunction "PB5/TIM3_CH2/SPI1_MOSI/SPI3_MOSI/CAN2_RX/I2C1_SMBA/OTG_HS_ULPI_D7/ETH_PPS_OUT/DCMI_D10/I2S3_SD_135") (pintype "passive"))
    )
    (net (code "79") (name "/PB6") (class "Default")
      (node (ref "J3") (pin "4") (pinfunction "4_4") (pintype "passive"))
      (node (ref "U4") (pin "136") (pinfunction "PB6/TIM4_CH1/U1_TX/CAN2_TX/I2C1_SCL/DCMI_D5_136") (pintype "passive"))
    )
    (net (code "80") (name "/PB7") (class "Default")
      (node (ref "J3") (pin "3") (pinfunction "3_3") (pintype "passive"))
      (node (ref "U4") (pin "137") (pinfunction "PB7/TIM4_CH2/U1_RX/FSMC_NL/I2C1_SDA/DCMI_VSYNC_137") (pintype "passive"))
    )
    (net (code "81") (name "/PB8") (class "Default")
      (node (ref "J3") (pin "2") (pinfunction "2_2") (pintype "passive"))
      (node (ref "U4") (pin "139") (pinfunction "PB8/TIM4_CH3/TIM10_CH1/CAN1_RX/SDIO_D4/ETH_MII_TXD3/I2C1_SCL/DCMI_D6_139") (pintype "passive"))
    )
    (net (code "82") (name "/PB9") (class "Default")
      (node (ref "J3") (pin "1") (pinfunction "1_1") (pintype "passive"))
      (node (ref "U4") (pin "140") (pinfunction "PB9/TIM4_CH4/TIM11_CH1/CAN1_TX/SDIO_D5/SPI2_NSS/I2C1_SDA/DCMI_D7/I2S2_WS_140") (pintype "passive"))
    )
    (net (code "83") (name "/PB10") (class "Default")
      (node (ref "J2") (pin "54") (pinfunction "54_54") (pintype "passive"))
      (node (ref "U4") (pin "69") (pinfunction "PB10/SPI2_SCK/TIM2_CH3/U3_TX/I2C2_SCL/OTG_HS_ULPI_D3/I2S2_CK_69") (pintype "passive"))
    )
    (net (code "84") (name "/PB11") (class "Default")
      (node (ref "J2") (pin "53") (pinfunction "53_53") (pintype "passive"))
      (node (ref "U4") (pin "70") (pinfunction "PB11/TIM2_CH4/U3_RX/I2C2_SDA/HS_ULPI_D4/ETH_MII_TX_EN/ETH_RMII_TX_EN_70") (pintype "passive"))
    )
    (net (code "85") (name "/PB12") (class "Default")
      (node (ref "J3") (pin "56") (pinfunction "56_56") (pintype "passive"))
      (node (ref "U4") (pin "73") (pinfunction "PB12/SPI2_NSS/TIM1_BKIN/U3_CK/CAN2_RX/I2C2_SMBA/OTG_HS_ULPI_D5/OTG_HS_ID/ETH_MII_TXD0/ETH_RMII_TXD0/I2S2_WS_73") (pintype "passive"))
    )
    (net (code "86") (name "/PB13") (class "Default")
      (node (ref "J3") (pin "55") (pinfunction "55_55") (pintype "passive"))
      (node (ref "U4") (pin "74") (pinfunction "PB13/SPI2_SCK/TIM1_CH1N/U3_CTS/CAN2_TX/OTG_HS_ULPI_D6/OTG_HS_VBUS/ETH_MII_TXD1/ETH_RMII_TXD1/I2S2_CK_74") (pintype "passive"))
    )
    (net (code "87") (name "/PC0") (class "Default")
      (node (ref "J2") (pin "19") (pinfunction "19_19") (pintype "passive"))
      (node (ref "U4") (pin "26") (pinfunction "PC0/OTG_HS_ULPI_STP/ADC123_IN10_26") (pintype "passive"))
    )
    (net (code "88") (name "/PC1") (class "Default")
      (node (ref "J2") (pin "22") (pinfunction "22_22") (pintype "passive"))
      (node (ref "U4") (pin "27") (pinfunction "PC1/ETH_MDC/ADC123_IN11_27") (pintype "passive"))
    )
    (net (code "89") (name "/PC2") (class "Default")
      (node (ref "J2") (pin "21") (pinfunction "21_21") (pintype "passive"))
      (node (ref "U4") (pin "28") (pinfunction "PC2/SPI2_MISO/OTG_HS_ULPI_DIR/ETH_MII_TXD2/I2S2ext_SD/ADC123_IN12_28") (pintype "passive"))
    )
    (net (code "90") (name "/PC3") (class "Default")
      (node (ref "J2") (pin "24") (pinfunction "24_24") (pintype "passive"))
      (node (ref "U4") (pin "29") (pinfunction "PC3/SPI2_MOSI/OTG_HS_ULPI_NXT/ETH_MII_TX_CLK/I2S2_SD/ADC123_IN13_29") (pintype "passive"))
    )
    (net (code "91") (name "/PC4") (class "Default")
      (node (ref "J2") (pin "31") (pinfunction "31_31") (pintype "passive"))
      (node (ref "U4") (pin "44") (pinfunction "PC4/ETH_MII_RXD0/ETH_RMII_RXD0/ADC12_IN14_44") (pintype "passive"))
    )
    (net (code "92") (name "/PC5") (class "Default")
      (node (ref "J2") (pin "34") (pinfunction "34_34") (pintype "passive"))
      (node (ref "U4") (pin "45") (pinfunction "PC5/ETH_MII_RXD1/ETH_RMII_RXD1/ADC12_IN15_45") (pintype "passive"))
    )
    (net (code "93") (name "/PC6") (class "Default")
      (node (ref "J3") (pin "37") (pinfunction "37_37") (pintype "passive"))
      (node (ref "U4") (pin "96") (pinfunction "PC6/TIM3_CH1/TIM8_CH1/U6_TX/SDIO_D6/DCMI_D0/I2S2_MCK_96") (pintype "passive"))
    )
    (net (code "94") (name "/PC7") (class "Default")
      (node (ref "J3") (pin "36") (pinfunction "36_36") (pintype "passive"))
      (node (ref "U4") (pin "97") (pinfunction "PC7/TIM3_CH2/TIM8_CH2/U6_RX/SDIO_D7/DCMI_D1/I2S3_MCK_97") (pintype "passive"))
    )
    (net (code "95") (name "/PC8") (class "Default")
      (node (ref "J3") (pin "35") (pinfunction "35_35") (pintype "passive"))
      (node (ref "U4") (pin "98") (pinfunction "PC8/TIM3_CH3/TIM8_CH3/U6_CK/SDIO_D0/DCMI_D2_98") (pintype "passive"))
    )
    (net (code "96") (name "/PC9") (class "Default")
      (node (ref "J3") (pin "34") (pinfunction "34_34") (pintype "passive"))
      (node (ref "U4") (pin "99") (pinfunction "PC9/TIM3_CH4/TIM8_CH4/I2C3_SDA/SDIO_D1/DCMI_D3/MCO2/I2S_CKIN_99") (pintype "passive"))
    )
    (net (code "97") (name "/PC10") (class "Default")
      (node (ref "J3") (pin "25") (pinfunction "25_25") (pintype "passive"))
      (node (ref "U4") (pin "111") (pinfunction "PC10/SPI3_SCK/U3_TX/U4_TX/SDIO_D2/DCMI_D8/I2S3_CK_111") (pintype "passive"))
    )
    (net (code "98") (name "/PC11") (class "Default")
      (node (ref "J3") (pin "24") (pinfunction "24_24") (pintype "passive"))
      (node (ref "U4") (pin "112") (pinfunction "PC11/SPI3_MISO/U3_RX/U4_RX/SDIO_D3/DCMI_D4/I2S3ext_SD_112") (pintype "passive"))
    )
    (net (code "99") (name "/PC12") (class "Default")
      (node (ref "J3") (pin "23") (pinfunction "23_23") (pintype "passive"))
      (node (ref "U4") (pin "113") (pinfunction "PC12/SPI3_MOSI/U3_CK/U5_TX/SDIO_CK/DCMI_D9/I2S3_SD_113") (pintype "passive"))
    )
    (net (code "100") (name "/PC13") (class "Default")
      (node (ref "J2") (pin "7") (pinfunction "7_7") (pintype "passive"))
      (node (ref "U4") (pin "7") (pinfunction "PC13/RTC_AF1_7") (pintype "passive"))
    )
    (net (code "101") (name "/PC14") (class "Default")
      (node (ref "C7") (pin "2") (pinfunction "2_2") (pintype "passive"))
      (node (ref "U4") (pin "8") (pinfunction "PC14-OSC32_IN_8") (pintype "passive"))
      (node (ref "Y1") (pin "2") (pinfunction "2_2") (pintype "passive"))
    )
    (net (code "102") (name "/PC15") (class "Default")
      (node (ref "C8") (pin "2") (pinfunction "2_2") (pintype "passive"))
      (node (ref "U4") (pin "9") (pinfunction "PC15-OSC32_OUT_9") (pintype "passive"))
      (node (ref "Y1") (pin "1") (pinfunction "1_1") (pintype "passive"))
    )
    (net (code "103") (name "/PD2") (class "Default")
      (node (ref "J3") (pin "20") (pinfunction "20_20") (pintype "passive"))
      (node (ref "U4") (pin "116") (pinfunction "PD2/TIM3_ETR/U5_RX/SDIO_CMD/DCMI_D11_116") (pintype "passive"))
    )
    (net (code "104") (name "/PD3") (class "Default")
      (node (ref "J3") (pin "19") (pinfunction "19_19") (pintype "passive"))
      (node (ref "U4") (pin "117") (pinfunction "PD3/FSMC_CLK/U2_CTS_117") (pintype "passive"))
    )
    (net (code "105") (name "/PD6") (class "Default")
      (node (ref "J3") (pin "16") (pinfunction "16_16") (pintype "passive"))
      (node (ref "U4") (pin "122") (pinfunction "PD6/FSMC_NWAIT/U2_RX_122") (pintype "passive"))
    )
    (net (code "106") (name "/PD7") (class "Default")
      (node (ref "J3") (pin "15") (pinfunction "15_15") (pintype "passive"))
      (node (ref "U4") (pin "123") (pinfunction "PD7/FSMC_NE1/FSMC_NCE2/U2_CK_123") (pintype "passive"))
    )
    (net (code "107") (name "/PE2") (class "Default")
      (node (ref "J2") (pin "4") (pinfunction "4_4") (pintype "passive"))
      (node (ref "U4") (pin "1") (pinfunction "PE2/TRACECLK/FSMC_A23/ETH_MII_TXD3_1") (pintype "passive"))
    )
    (net (code "108") (name "/PF6") (class "Default")
      (node (ref "J2") (pin "16") (pinfunction "16_16") (pintype "passive"))
      (node (ref "U4") (pin "18") (pinfunction "PF6/TIM10_CH1/FSMC_NIORD/ADC3_IN4_18") (pintype "passive"))
    )
    (net (code "109") (name "/PF7") (class "Default")
      (node (ref "J2") (pin "15") (pinfunction "15_15") (pintype "passive"))
      (node (ref "U4") (pin "19") (pinfunction "PF7/TIM11_CH1/FSMC_NREG/ADC3_IN5_19") (pintype "passive"))
    )
    (net (code "110") (name "/PF8") (class "Default")
      (node (ref "J2") (pin "18") (pinfunction "18_18") (pintype "passive"))
      (node (ref "U4") (pin "20") (pinfunction "PF8/TIM13_CH1/FSMC_NIOWR/ADC3_IN6_20") (pintype "passive"))
    )
    (net (code "111") (name "/PF11") (class "Default")
      (node (ref "J2") (pin "38") (pinfunction "38_38") (pintype "passive"))
      (node (ref "U4") (pin "49") (pinfunction "PF11/DCMI_D12_49") (pintype "passive"))
    )
    (net (code "112") (name "/PG9") (class "Default")
      (node (ref "J3") (pin "14") (pinfunction "14_14") (pintype "passive"))
      (node (ref "U4") (pin "124") (pinfunction "PG9/FSMC_NE2/FSMC_NCE3/U6_RX_124") (pintype "passive"))
    )
    (net (code "113") (name "/PG11") (class "Default")
      (node (ref "J3") (pin "12") (pinfunction "12_12") (pintype "passive"))
      (node (ref "U4") (pin "126") (pinfunction "PG11/FSMC_NCE4_2/ETH_MII_TX_EN/ETH_RMII_TX_EN_126") (pintype "passive"))
    )
    (net (code "114") (name "/PG13") (class "Default")
      (node (ref "J3") (pin "10") (pinfunction "10_10") (pintype "passive"))
      (node (ref "U4") (pin "128") (pinfunction "PG13/FSMC_A24/U6_CTS/ETH_MII_TXD0/ETH_RMII_TXD0_128") (pintype "passive"))
    )
    (net (code "115") (name "/PG14") (class "Default")
      (node (ref "J3") (pin "9") (pinfunction "9_9") (pintype "passive"))
      (node (ref "U4") (pin "129") (pinfunction "PG14/FSMC_A25/U6_TX/ETH_MII_TXD1/ETH_RMII_TXD1_129") (pintype "passive"))
    )
    (net (code "116") (name "/PG15") (class "Default")
      (node (ref "J3") (pin "8") (pinfunction "8_8") (pintype "passive"))
      (node (ref "U4") (pin "132") (pinfunction "PG15/U6_CTS/DCMI_D13_132") (pintype "passive"))
    )
    (net (code "117") (name "/RST") (class "Default")
      (node (ref "C14") (pin "2") (pinfunction "2_2") (pintype "passive"))
      (node (ref "J1") (pin "15") (pinfunction "nSRST_15") (pintype "passive"))
      (node (ref "R24") (pin "1") (pinfunction "1_1") (pintype "passive"))
      (node (ref "RST") (pin "1") (pinfunction "C1_1") (pintype "passive"))
      (node (ref "U4") (pin "25") (pinfunction "NRST_25") (pintype "passive"))
    )
    (net (code "118") (name "/VBAT") (class "Default")
      (node (ref "U4") (pin "6") (pinfunction "VBAT_6") (pintype "passive"))
    )
    (net (code "119") (name "/VREF+") (class "Default")
      (node (ref "C33") (pin "1") (pinfunction "1_1") (pintype "passive"))
      (node (ref "J2") (pin "56") (pinfunction "56_56") (pintype "passive"))
      (node (ref "R21") (pin "1") (pinfunction "1_1") (pintype "passive"))
      (node (ref "U4") (pin "32") (pinfunction "Vref+_32") (pintype "passive"))
    )
    (net (code "120") (name "3V3") (class "Default")
      (node (ref "C2") (pin "2") (pinfunction "2_2") (pintype "passive"))
      (node (ref "C20") (pin "1") (pinfunction "1_1") (pintype "passive"))
      (node (ref "C21") (pin "1") (pinfunction "1_1") (pintype "passive"))
      (node (ref "C22") (pin "1") (pinfunction "1_1") (pintype "passive"))
      (node (ref "C23") (pin "1") (pinfunction "1_1") (pintype "passive"))
      (node (ref "C24") (pin "1") (pinfunction "1_1") (pintype "passive"))
      (node (ref "C25") (pin "1") (pinfunction "1_1") (pintype "passive"))
      (node (ref "C26") (pin "1") (pinfunction "1_1") (pintype "passive"))
      (node (ref "C27") (pin "1") (pinfunction "1_1") (pintype "passive"))
      (node (ref "C28") (pin "1") (pinfunction "1_1") (pintype "passive"))
      (node (ref "C29") (pin "1") (pinfunction "1_1") (pintype "passive"))
      (node (ref "C30") (pin "1") (pinfunction "1_1") (pintype "passive"))
      (node (ref "C31") (pin "1") (pinfunction "1_1") (pintype "passive"))
      (node (ref "C32") (pin "1") (pinfunction "1_1") (pintype "passive"))
      (node (ref "J1") (pin "1") (pinfunction "Vref_1") (pintype "passive"))
      (node (ref "J1") (pin "2") (pinfunction "Vsupply_2") (pintype "passive"))
      (node (ref "J2") (pin "59") (pinfunction "59_59") (pintype "passive"))
      (node (ref "J2") (pin "60") (pinfunction "60_60") (pintype "passive"))
      (node (ref "J3") (pin "57") (pinfunction "57_57") (pintype "passive"))
      (node (ref "R15") (pin "1") (pinfunction "1_1") (pintype "passive"))
      (node (ref "R17") (pin "1") (pinfunction "1_1") (pintype "passive"))
      (node (ref "R18") (pin "1") (pinfunction "1_1") (pintype "passive"))
      (node (ref "R19") (pin "1") (pinfunction "1_1") (pintype "passive"))
      (node (ref "R22") (pin "2") (pinfunction "2_2") (pintype "passive"))
      (node (ref "R23") (pin "1") (pinfunction "1_1") (pintype "passive"))
      (node (ref "R24") (pin "2") (pinfunction "2_2") (pintype "passive"))
      (node (ref "R28") (pin "2") (pinfunction "2_2") (pintype "passive"))
      (node (ref "U4") (pin "108") (pinfunction "VDD_108") (pintype "passive"))
      (node (ref "U4") (pin "121") (pinfunction "VDD_121") (pintype "passive"))
      (node (ref "U4") (pin "131") (pinfunction "VDD_131") (pintype "passive"))
      (node (ref "U4") (pin "144") (pinfunction "VDD_144") (pintype "passive"))
      (node (ref "U4") (pin "17") (pinfunction "VDD_17") (pintype "passive"))
      (node (ref "U4") (pin "30") (pinfunction "VDD_30") (pintype "passive"))
      (node (ref "U4") (pin "39") (pinfunction "VDD_39") (pintype "passive"))
      (node (ref "U4") (pin "52") (pinfunction "VDD_52") (pintype "passive"))
      (node (ref "U4") (pin "62") (pinfunction "VDD_62") (pintype "passive"))
      (node (ref "U4") (pin "72") (pinfunction "VDD_72") (pintype "passive"))
      (node (ref "U4") (pin "84") (pinfunction "VDD_84") (pintype "passive"))
      (node (ref "U4") (pin "95") (pinfunction "VDD_95") (pintype "passive"))
    )
    (net (code "121") (name "5V") (class "Default")
      (node (ref "J3") (pin "59") (pinfunction "59_59") (pintype "passive"))
      (node (ref "R11") (pin "1") (pinfunction "1_1") (pintype "passive"))
    )
    (net (code "122") (name "GND") (class "Default")
      (node (ref "C10") (pin "2") (pinfunction "2_2") (pintype "passive"))
      (node (ref "C11") (pin "2") (pinfunction "2_2") (pintype "passive"))
      (node (ref "C12") (pin "2") (pinfunction "2_2") (pintype "passive"))
      (node (ref "C14") (pin "1") (pinfunction "1_1") (pintype "passive"))
      (node (ref "C15") (pin "1") (pinfunction "1_1") (pintype "passive"))
      (node (ref "C16") (pin "1") (pinfunction "1_1") (pintype "passive"))
      (node (ref "C2") (pin "1") (pinfunction "1_1") (pintype "passive"))
      (node (ref "C20") (pin "2") (pinfunction "2_2") (pintype "passive"))
      (node (ref "C21") (pin "2") (pinfunction "2_2") (pintype "passive"))
      (node (ref "C22") (pin "2") (pinfunction "2_2") (pintype "passive"))
      (node (ref "C23") (pin "2") (pinfunction "2_2") (pintype "passive"))
      (node (ref "C24") (pin "2") (pinfunction "2_2") (pintype "passive"))
      (node (ref "C25") (pin "2") (pinfunction "2_2") (pintype "passive"))
      (node (ref "C26") (pin "2") (pinfunction "2_2") (pintype "passive"))
      (node (ref "C27") (pin "2") (pinfunction "2_2") (pintype "passive"))
      (node (ref "C28") (pin "2") (pinfunction "2_2") (pintype "passive"))
      (node (ref "C29") (pin "2") (pinfunction "2_2") (pintype "passive"))
      (node (ref "C30") (pin "2") (pinfunction "2_2") (pintype "passive"))
      (node (ref "C31") (pin "2") (pinfunction "2_2") (pintype "passive"))
      (node (ref "C32") (pin "2") (pinfunction "2_2") (pintype "passive"))
      (node (ref "C33") (pin "2") (pinfunction "2_2") (pintype "passive"))
      (node (ref "C7") (pin "1") (pinfunction "1_1") (pintype "passive"))
      (node (ref "C8") (pin "1") (pinfunction "1_1") (pintype "passive"))
      (node (ref "C9") (pin "2") (pinfunction "2_2") (pintype "passive"))
      (node (ref "J1") (pin "10") (pinfunction "GND_10") (pintype "passive"))
      (node (ref "J1") (pin "12") (pinfunction "GND_12") (pintype "passive"))
      (node (ref "J1") (pin "14") (pinfunction "GND_14") (pintype "passive"))
      (node (ref "J1") (pin "16") (pinfunction "GND_16") (pintype "passive"))
      (node (ref "J1") (pin "18") (pinfunction "GND_18") (pintype "passive"))
      (node (ref "J1") (pin "20") (pinfunction "GND_20") (pintype "passive"))
      (node (ref "J1") (pin "4") (pinfunction "GND_4") (pintype "passive"))
      (node (ref "J1") (pin "6") (pinfunction "GND_6") (pintype "passive"))
      (node (ref "J1") (pin "8") (pinfunction "GND_8") (pintype "passive"))
      (node (ref "J2") (pin "55") (pinfunction "55_55") (pintype "passive"))
      (node (ref "J3") (pin "58") (pinfunction "58_58") (pintype "passive"))
      (node (ref "J3") (pin "60") (pinfunction "60_60") (pintype "passive"))
      (node (ref "R12") (pin "2") (pinfunction "2_2") (pintype "passive"))
      (node (ref "R13") (pin "2") (pinfunction "2_2") (pintype "passive"))
      (node (ref "R14") (pin "2") (pinfunction "2_2") (pintype "passive"))
      (node (ref "R16") (pin "1") (pinfunction "1_1") (pintype "passive"))
      (node (ref "R25") (pin "2") (pinfunction "2_2") (pintype "passive"))
      (node (ref "R26") (pin "2") (pinfunction "2_2") (pintype "passive"))
      (node (ref "R7") (pin "2") (pinfunction "2_2") (pintype "passive"))
      (node (ref "RST") (pin "2") (pinfunction "C2_2") (pintype "passive"))
      (node (ref "U1") (pin "1") (pinfunction "GND_1") (pintype "passive"))
      (node (ref "U10") (pin "2") (pinfunction "GND_2") (pintype "passive"))
      (node (ref "U11") (pin "2") (pinfunction "GND_2") (pintype "passive"))
      (node (ref "U12") (pin "2") (pinfunction "GND_2") (pintype "passive"))
      (node (ref "U13") (pin "2") (pinfunction "GND_2") (pintype "passive"))
      (node (ref "U14") (pin "9") (pinfunction "GND_9") (pintype "passive"))
      (node (ref "U15") (pin "2") (pinfunction "GND_2") (pintype "passive"))
      (node (ref "U15") (pin "4") (pinfunction "GND_4") (pintype "passive"))
      (node (ref "U16") (pin "2") (pinfunction "GND_2") (pintype "passive"))
      (node (ref "U16") (pin "4") (pinfunction "GND_4") (pintype "passive"))
      (node (ref "U17") (pin "2") (pinfunction "GND_2") (pintype "passive"))
      (node (ref "U17") (pin "4") (pinfunction "GND_4") (pintype "passive"))
      (node (ref "U18") (pin "18") (pinfunction "GND_18") (pintype "passive"))
      (node (ref "U2") (pin "1") (pinfunction "GND_1") (pintype "passive"))
      (node (ref "U23") (pin "2") (pinfunction "GND_2") (pintype "passive"))
      (node (ref "U25") (pin "3") (pinfunction "GND_3") (pintype "passive"))
      (node (ref "U3") (pin "2") (pinfunction "GND_2") (pintype "passive"))
      (node (ref "U4") (pin "107") (pinfunction "VSS_107") (pintype "passive"))
      (node (ref "U4") (pin "120") (pinfunction "VSS_120") (pintype "passive"))
      (node (ref "U4") (pin "130") (pinfunction "VSS_130") (pintype "passive"))
      (node (ref "U4") (pin "16") (pinfunction "VSS_16") (pintype "passive"))
      (node (ref "U4") (pin "31") (pinfunction "VSSA_31") (pintype "passive"))
      (node (ref "U4") (pin "38") (pinfunction "VSS_38") (pintype "passive"))
      (node (ref "U4") (pin "51") (pinfunction "VSS_51") (pintype "passive"))
      (node (ref "U4") (pin "61") (pinfunction "VSS_61") (pintype "passive"))
      (node (ref "U4") (pin "83") (pinfunction "VSS_83") (pintype "passive"))
      (node (ref "U4") (pin "94") (pinfunction "VSS_94") (pintype "passive"))
      (node (ref "U5") (pin "2") (pinfunction "GND_2") (pintype "passive"))
      (node (ref "U6") (pin "2") (pinfunction "GND_2") (pintype "passive"))
      (node (ref "U7") (pin "2") (pinfunction "GND_2") (pintype "passive"))
      (node (ref "U8") (pin "2") (pinfunction "GND_2") (pintype "passive"))
      (node (ref "U9") (pin "2") (pinfunction "GND_2") (pintype "passive"))
      (node (ref "USB1") (pin "7") (pinfunction "EH_7") (pintype "passive"))
      (node (ref "USB1") (pin "8") (pinfunction "EH_8") (pintype "passive"))
      (node (ref "USB1") (pin "A12") (pinfunction "GND_A12") (pintype "passive"))
      (node (ref "USB1") (pin "B12") (pinfunction "GND_B12") (pintype "passive"))
    )
    (net (code "123") (name "Net-(D1-Pad2)") (class "Default")
      (node (ref "D1") (pin "2") (pinfunction "2_2") (pintype "passive"))
      (node (ref "USB1") (pin "B9") (pinfunction "VBUS_B9") (pintype "passive"))
    )
    (net (code "124") (name "Net-(J2-Pad57)") (class "Default")
      (node (ref "J2") (pin "57") (pinfunction "57_57") (pintype "passive"))
      (node (ref "R10") (pin "1") (pinfunction "1_1") (pintype "passive"))
    )
    (net (code "125") (name "Net-(R7-Pad1)") (class "Default")
      (node (ref "R7") (pin "1") (pinfunction "1_1") (pintype "passive"))
      (node (ref "R9") (pin "2") (pinfunction "2_2") (pintype "passive"))
    )
    (net (code "126") (name "Net-(R11-Pad2)") (class "Default")
      (node (ref "R11") (pin "2") (pinfunction "2_2") (pintype "passive"))
      (node (ref "R14") (pin "1") (pinfunction "1_1") (pintype "passive"))
    )
    (net (code "127") (name "Net-(R13-Pad1)") (class "Default")
      (node (ref "R13") (pin "1") (pinfunction "1_1") (pintype "passive"))
      (node (ref "R15") (pin "2") (pinfunction "2_2") (pintype "passive"))
    )
    (net (code "128") (name "Net-(U4-PDR_ON)") (class "Default")
      (node (ref "R26") (pin "1") (pinfunction "1_1") (pintype "passive"))
      (node (ref "R28") (pin "1") (pinfunction "1_1") (pintype "passive"))
      (node (ref "U4") (pin "143") (pinfunction "PDR_ON_143") (pintype "passive"))
    )
    (net (code "129") (name "Net-(U4-PH0-OSC_IN)") (class "Default")
      (node (ref "C10") (pin "1") (pinfunction "1_1") (pintype "passive"))
      (node (ref "R20") (pin "1") (pinfunction "1_1") (pintype "passive"))
      (node (ref "U4") (pin "23") (pinfunction "PH0-OSC_IN_23") (pintype "passive"))
      (node (ref "Y2") (pin "1") (pinfunction "1_1") (pintype "passive"))
    )
    (net (code "130") (name "Net-(U4-PH1-OSC_OUT)") (class "Default")
      (node (ref "C9") (pin "1") (pinfunction "1_1") (pintype "passive"))
      (node (ref "R20") (pin "2") (pinfunction "2_2") (pintype "passive"))
      (node (ref "U4") (pin "24") (pinfunction "PH1-OSC_OUT_24") (pintype "passive"))
      (node (ref "Y2") (pin "2") (pinfunction "2_2") (pintype "passive"))
    )
    (net (code "131") (name "Net-(U4-Vcap_1)") (class "Default")
      (node (ref "C11") (pin "1") (pinfunction "1_1") (pintype "passive"))
      (node (ref "U4") (pin "71") (pinfunction "Vcap_1_71") (pintype "passive"))
    )
    (net (code "132") (name "Net-(U4-Vcap_2)") (class "Default")
      (node (ref "C12") (pin "1") (pinfunction "1_1") (pintype "passive"))
      (node (ref "U4") (pin "106") (pinfunction "Vcap_2_106") (pintype "passive"))
    )
    (net (code "133") (name "Net-(U10-DATA)") (class "Default")
      (node (ref "U10") (pin "3") (pinfunction "DATA_3") (pintype "passive"))
      (node (ref "U18") (pin "2") (pinfunction "D2_2") (pintype "passive"))
    )
    (net (code "134") (name "Net-(U11-DATA)") (class "Default")
      (node (ref "U11") (pin "3") (pinfunction "DATA_3") (pintype "passive"))
      (node (ref "U18") (pin "1") (pinfunction "D1_1") (pintype "passive"))
    )
    (net (code "135") (name "Net-(U12-DATA)") (class "Default")
      (node (ref "U12") (pin "3") (pinfunction "DATA_3") (pintype "passive"))
      (node (ref "U18") (pin "3") (pinfunction "D3_3") (pintype "passive"))
    )
    (net (code "136") (name "Net-(U13-DATA)") (class "Default")
      (node (ref "U13") (pin "3") (pinfunction "DATA_3") (pintype "passive"))
      (node (ref "U18") (pin "4") (pinfunction "D4_4") (pintype "passive"))
    )
    (net (code "137") (name "Net-(U19-D)") (class "Default")
      (node (ref "U19") (pin "4") (pinfunction "D_4") (pintype "passive"))
      (node (ref "U21") (pin "3") (pinfunction "C_3") (pintype "passive"))
    )
    (net (code "138") (name "Net-(U20-D)") (class "Default")
      (node (ref "U20") (pin "4") (pinfunction "D_4") (pintype "passive"))
      (node (ref "U22") (pin "3") (pinfunction "C_3") (pintype "passive"))
    )
    (net (code "139") (name "Net-(U23-RS232.RXD)") (class "Default")
      (node (ref "U23") (pin "8") (pinfunction "RS232.RXD_8") (pintype "passive"))
      (node (ref "U24") (pin "4") (pinfunction "RX_4") (pintype "passive"))
    )
    (net (code "140") (name "Net-(U23-RS232.TXD)") (class "Default")
      (node (ref "U23") (pin "7") (pinfunction "RS232.TXD_7") (pintype "passive"))
      (node (ref "U24") (pin "3") (pinfunction "TX_3") (pintype "passive"))
    )
    (net (code "141") (name "Net-(U24-5V)") (class "Default")
      (node (ref "U23") (pin "5") (pinfunction "VCC_5") (pintype "passive"))
      (node (ref "U24") (pin "1") (pinfunction "5V_1") (pintype "passive"))
    )
    (net (code "142") (name "Net-(U24-GND)") (class "Default")
      (node (ref "U23") (pin "6") (pinfunction "GND_6") (pintype "passive"))
      (node (ref "U24") (pin "2") (pinfunction "GND_2") (pintype "passive"))
    )
    (net (code "143") (name "Net-(U25-UD+)") (class "Default")
      (node (ref "U25") (pin "1") (pinfunction "UD+_1") (pintype "passive"))
      (node (ref "USB1") (pin "B5") (pinfunction "D+_B5") (pintype "passive"))
    )
    (net (code "144") (name "Net-(U25-UD-)") (class "Default")
      (node (ref "U25") (pin "2") (pinfunction "UD-_2") (pintype "passive"))
      (node (ref "USB1") (pin "A5") (pinfunction "D-_A5") (pintype "passive"))
    )
    (net (code "145") (name "Net-(U25-VCC)") (class "Default")
      (node (ref "D1") (pin "1") (pinfunction "1_1") (pintype "passive"))
      (node (ref "U25") (pin "5") (pinfunction "VCC_5") (pintype "passive"))
    )
    (net (code "146") (name "VCC") (class "Default")
      (node (ref "R9") (pin "1") (pinfunction "1_1") (pintype "passive"))
      (node (ref "U15") (pin "1") (pinfunction "VIN_1") (pintype "passive"))
      (node (ref "U16") (pin "1") (pinfunction "VIN_1") (pintype "passive"))
      (node (ref "U17") (pin "1") (pinfunction "VIN_1") (pintype "passive"))
      (node (ref "U3") (pin "1") (pinfunction "V+_1") (pintype "passive"))
      (node (ref "U5") (pin "1") (pinfunction "V+_1") (pintype "passive"))
      (node (ref "U6") (pin "1") (pinfunction "V+_1") (pintype "passive"))
      (node (ref "U7") (pin "1") (pinfunction "V+_1") (pintype "passive"))
    )
    (net (code "147") (name "VDDA") (class "Default")
      (node (ref "C15") (pin "2") (pinfunction "2_2") (pintype "passive"))
      (node (ref "C16") (pin "2") (pinfunction "2_2") (pintype "passive"))
      (node (ref "R21") (pin "2") (pinfunction "2_2") (pintype "passive"))
      (node (ref "R22") (pin "1") (pinfunction "1_1") (pintype "passive"))
      (node (ref "U4") (pin "33") (pinfunction "VDDA_33") (pintype "passive"))
    )
    (net (code "148") (name "unconnected-(J1-NC-Pad17)") (class "Default")
      (node (ref "J1") (pin "17") (pinfunction "NC_17") (pintype "passive"))
    )
    (net (code "149") (name "unconnected-(J1-NC-Pad19)") (class "Default")
      (node (ref "J1") (pin "19") (pinfunction "NC_19") (pintype "passive"))
    )
    (net (code "150") (name "unconnected-(J1-RTCK-Pad11)") (class "Default")
      (node (ref "J1") (pin "11") (pinfunction "RTCK_11") (pintype "passive"))
    )
    (net (code "151") (name "unconnected-(U1-SCL-Pad3)") (class "Default")
      (node (ref "U1") (pin "3") (pinfunction "SCL_3") (pintype "passive"))
    )
    (net (code "152") (name "unconnected-(U1-SDA-Pad4)") (class "Default")
      (node (ref "U1") (pin "4") (pinfunction "SDA_4") (pintype "passive"))
    )
    (net (code "153") (name "unconnected-(U2-RX-Pad2)") (class "Default")
      (node (ref "U2") (pin "2") (pinfunction "RX_2") (pintype "passive"))
    )
    (net (code "154") (name "unconnected-(U2-TX-Pad3)") (class "Default")
      (node (ref "U2") (pin "3") (pinfunction "TX_3") (pintype "passive"))
    )
    (net (code "155") (name "unconnected-(U3-Com-Pad3)") (class "Default")
      (node (ref "U3") (pin "3") (pinfunction "Com_3") (pintype "passive+no_connect"))
    )
    (net (code "156") (name "unconnected-(U3-Dir-Pad6)") (class "Default")
      (node (ref "U3") (pin "6") (pinfunction "Dir_6") (pintype "passive"))
    )
    (net (code "157") (name "unconnected-(U3-En-Pad4)") (class "Default")
      (node (ref "U3") (pin "4") (pinfunction "En_4") (pintype "passive"))
    )
    (net (code "158") (name "unconnected-(U3-Stp-Pad5)") (class "Default")
      (node (ref "U3") (pin "5") (pinfunction "Stp_5") (pintype "passive"))
    )
    (net (code "159") (name "unconnected-(U5-Com-Pad3)") (class "Default")
      (node (ref "U5") (pin "3") (pinfunction "Com_3") (pintype "passive+no_connect"))
    )
    (net (code "160") (name "unconnected-(U5-Dir-Pad6)") (class "Default")
      (node (ref "U5") (pin "6") (pinfunction "Dir_6") (pintype "passive"))
    )
    (net (code "161") (name "unconnected-(U5-En-Pad4)") (class "Default")
      (node (ref "U5") (pin "4") (pinfunction "En_4") (pintype "passive"))
    )
    (net (code "162") (name "unconnected-(U5-Stp-Pad5)") (class "Default")
      (node (ref "U5") (pin "5") (pinfunction "Stp_5") (pintype "passive"))
    )
    (net (code "163") (name "unconnected-(U6-Com-Pad3)") (class "Default")
      (node (ref "U6") (pin "3") (pinfunction "Com_3") (pintype "passive+no_connect"))
    )
    (net (code "164") (name "unconnected-(U6-Dir-Pad6)") (class "Default")
      (node (ref "U6") (pin "6") (pinfunction "Dir_6") (pintype "passive"))
    )
    (net (code "165") (name "unconnected-(U6-En-Pad4)") (class "Default")
      (node (ref "U6") (pin "4") (pinfunction "En_4") (pintype "passive"))
    )
    (net (code "166") (name "unconnected-(U6-Stp-Pad5)") (class "Default")
      (node (ref "U6") (pin "5") (pinfunction "Stp_5") (pintype "passive"))
    )
    (net (code "167") (name "unconnected-(U7-Com-Pad3)") (class "Default")
      (node (ref "U7") (pin "3") (pinfunction "Com_3") (pintype "passive+no_connect"))
    )
    (net (code "168") (name "unconnected-(U7-Dir-Pad6)") (class "Default")
      (node (ref "U7") (pin "6") (pinfunction "Dir_6") (pintype "passive"))
    )
    (net (code "169") (name "unconnected-(U7-En-Pad4)") (class "Default")
      (node (ref "U7") (pin "4") (pinfunction "En_4") (pintype "passive"))
    )
    (net (code "170") (name "unconnected-(U7-Stp-Pad5)") (class "Default")
      (node (ref "U7") (pin "5") (pinfunction "Stp_5") (pintype "passive"))
    )
    (net (code "171") (name "unconnected-(U8-DATA-Pad3)") (class "Default")
      (node (ref "U8") (pin "3") (pinfunction "DATA_3") (pintype "passive"))
    )
    (net (code "172") (name "unconnected-(U9-DATA-Pad3)") (class "Default")
      (node (ref "U9") (pin "3") (pinfunction "DATA_3") (pintype "passive"))
    )
    (net (code "173") (name "unconnected-(U14-3V3_OUT-Pad8)") (class "Default")
      (node (ref "U14") (pin "8") (pinfunction "3V3_OUT_8") (pintype "passive+no_connect"))
    )
    (net (code "174") (name "unconnected-(U14-BOOT0-Pad15)") (class "Default")
      (node (ref "U14") (pin "15") (pinfunction "BOOT0_15") (pintype "passive+no_connect"))
    )
    (net (code "175") (name "unconnected-(U14-FRAMESYNC-Pad14)") (class "Default")
      (node (ref "U14") (pin "14") (pinfunction "FRAMESYNC_14") (pintype "passive+no_connect"))
    )
    (net (code "176") (name "unconnected-(U14-P0{slash}UART1_RX-Pad1)") (class "Default")
      (node (ref "U14") (pin "1") (pinfunction "P0/UART1_RX_1") (pintype "passive+no_connect"))
    )
    (net (code "177") (name "unconnected-(U14-P1{slash}UART1_TX-Pad2)") (class "Default")
      (node (ref "U14") (pin "2") (pinfunction "P1/UART1_TX_2") (pintype "passive+no_connect"))
    )
    (net (code "178") (name "unconnected-(U14-P2{slash}CAN2_TX-Pad3)") (class "Default")
      (node (ref "U14") (pin "3") (pinfunction "P2/CAN2_TX_3") (pintype "passive+no_connect"))
    )
    (net (code "179") (name "unconnected-(U14-P3{slash}CAN2_RX-Pad4)") (class "Default")
      (node (ref "U14") (pin "4") (pinfunction "P3/CAN2_RX_4") (pintype "passive+no_connect"))
    )
    (net (code "180") (name "unconnected-(U14-P4{slash}UART3_TX-Pad5)") (class "Default")
      (node (ref "U14") (pin "5") (pinfunction "P4/UART3_TX_5") (pintype "passive"))
    )
    (net (code "181") (name "unconnected-(U14-P5{slash}UART3_RX-Pad6)") (class "Default")
      (node (ref "U14") (pin "6") (pinfunction "P5/UART3_RX_6") (pintype "passive"))
    )
    (net (code "182") (name "unconnected-(U14-P6-Pad7)") (class "Default")
      (node (ref "U14") (pin "7") (pinfunction "P6_7") (pintype "passive+no_connect"))
    )
    (net (code "183") (name "unconnected-(U14-P7-Pad11)") (class "Default")
      (node (ref "U14") (pin "11") (pinfunction "P7_11") (pintype "passive+no_connect"))
    )
    (net (code "184") (name "unconnected-(U14-P8-Pad12)") (class "Default")
      (node (ref "U14") (pin "12") (pinfunction "P8_12") (pintype "passive+no_connect"))
    )
    (net (code "185") (name "unconnected-(U14-P9-Pad13)") (class "Default")
      (node (ref "U14") (pin "13") (pinfunction "P9_13") (pintype "passive+no_connect"))
    )
    (net (code "186") (name "unconnected-(U14-Reset-Pad16)") (class "Default")
      (node (ref "U14") (pin "16") (pinfunction "Reset_16") (pintype "passive+no_connect"))
    )
    (net (code "187") (name "unconnected-(U18-3V3-Pad21)") (class "Default")
      (node (ref "U18") (pin "21") (pinfunction "3V3_21") (pintype "passive+no_connect"))
    )
    (net (code "188") (name "unconnected-(U18-D5-Pad5)") (class "Default")
      (node (ref "U18") (pin "5") (pinfunction "D5_5") (pintype "passive+no_connect"))
    )
    (net (code "189") (name "unconnected-(U18-D6-Pad6)") (class "Default")
      (node (ref "U18") (pin "6") (pinfunction "D6_6") (pintype "passive+no_connect"))
    )
    (net (code "190") (name "unconnected-(U18-D7-Pad7)") (class "Default")
      (node (ref "U18") (pin "7") (pinfunction "D7_7") (pintype "passive+no_connect"))
    )
    (net (code "191") (name "unconnected-(U18-D8-Pad8)") (class "Default")
      (node (ref "U18") (pin "8") (pinfunction "D8_8") (pintype "passive+no_connect"))
    )
    (net (code "192") (name "unconnected-(U18-D9-Pad9)") (class "Default")
      (node (ref "U18") (pin "9") (pinfunction "D9_9") (pintype "passive+no_connect"))
    )
    (net (code "193") (name "unconnected-(U18-D10-Pad10)") (class "Default")
      (node (ref "U18") (pin "10") (pinfunction "D10_10") (pintype "passive+no_connect"))
    )
    (net (code "194") (name "unconnected-(U18-D11-Pad11)") (class "Default")
      (node (ref "U18") (pin "11") (pinfunction "D11_11") (pintype "passive+no_connect"))
    )
    (net (code "195") (name "unconnected-(U18-D12-Pad12)") (class "Default")
      (node (ref "U18") (pin "12") (pinfunction "D12_12") (pintype "passive+no_connect"))
    )
    (net (code "196") (name "unconnected-(U18-D13-Pad13)") (class "Default")
      (node (ref "U18") (pin "13") (pinfunction "D13_13") (pintype "passive+no_connect"))
    )
    (net (code "197") (name "unconnected-(U18-D14-Pad14)") (class "Default")
      (node (ref "U18") (pin "14") (pinfunction "D14_14") (pintype "passive+no_connect"))
    )
    (net (code "198") (name "unconnected-(U18-D15-Pad15)") (class "Default")
      (node (ref "U18") (pin "15") (pinfunction "D15_15") (pintype "passive+no_connect"))
    )
    (net (code "199") (name "unconnected-(U18-D16-Pad16)") (class "Default")
      (node (ref "U18") (pin "16") (pinfunction "D16_16") (pintype "passive+no_connect"))
    )
    (net (code "200") (name "unconnected-(U18-RX-Pad20)") (class "Default")
      (node (ref "U18") (pin "20") (pinfunction "RX_20") (pintype "passive"))
    )
    (net (code "201") (name "unconnected-(U18-TX-Pad19)") (class "Default")
      (node (ref "U18") (pin "19") (pinfunction "TX_19") (pintype "passive"))
    )
    (net (code "202") (name "unconnected-(U19-A-Pad1)") (class "Default")
      (node (ref "U19") (pin "1") (pinfunction "A_1") (pintype "passive"))
    )
    (net (code "203") (name "unconnected-(U19-B-Pad2)") (class "Default")
      (node (ref "U19") (pin "2") (pinfunction "B_2") (pintype "passive"))
    )
    (net (code "204") (name "unconnected-(U20-A-Pad1)") (class "Default")
      (node (ref "U20") (pin "1") (pinfunction "A_1") (pintype "passive"))
    )
    (net (code "205") (name "unconnected-(U20-B-Pad2)") (class "Default")
      (node (ref "U20") (pin "2") (pinfunction "B_2") (pintype "passive"))
    )
    (net (code "206") (name "unconnected-(U21-A-Pad1)") (class "Default")
      (node (ref "U21") (pin "1") (pinfunction "A_1") (pintype "passive"))
    )
    (net (code "207") (name "unconnected-(U21-B-Pad2)") (class "Default")
      (node (ref "U21") (pin "2") (pinfunction "B_2") (pintype "passive"))
    )
    (net (code "208") (name "unconnected-(U21-D-Pad4)") (class "Default")
      (node (ref "U21") (pin "4") (pinfunction "D_4") (pintype "passive"))
    )
    (net (code "209") (name "unconnected-(U22-A-Pad1)") (class "Default")
      (node (ref "U22") (pin "1") (pinfunction "A_1") (pintype "passive"))
    )
    (net (code "210") (name "unconnected-(U22-B-Pad2)") (class "Default")
      (node (ref "U22") (pin "2") (pinfunction "B_2") (pintype "passive"))
    )
    (net (code "211") (name "unconnected-(U22-D-Pad4)") (class "Default")
      (node (ref "U22") (pin "4") (pinfunction "D_4") (pintype "passive"))
    )
    (net (code "212") (name "unconnected-(U23-TTL.RXD-Pad4)") (class "Default")
      (node (ref "U23") (pin "4") (pinfunction "TTL.RXD_4") (pintype "passive"))
    )
    (net (code "213") (name "unconnected-(U23-TTL.TXD-Pad3)") (class "Default")
      (node (ref "U23") (pin "3") (pinfunction "TTL.TXD_3") (pintype "passive"))
    )
    (net (code "214") (name "unconnected-(U25-RTS#-Pad4)") (class "Default")
      (node (ref "U25") (pin "4") (pinfunction "RTS#_4") (pintype "passive+no_connect"))
    )
    (net (code "215") (name "unconnected-(U25-RXD-Pad7)") (class "Default")
      (node (ref "U25") (pin "7") (pinfunction "RXD_7") (pintype "passive"))
    )
    (net (code "216") (name "unconnected-(U25-TXD-Pad6)") (class "Default")
      (node (ref "U25") (pin "6") (pinfunction "TXD_6") (pintype "passive"))
    )
    (net (code "217") (name "unconnected-(U25-V3-Pad8)") (class "Default")
      (node (ref "U25") (pin "8") (pinfunction "V3_8") (pintype "passive+no_connect"))
    )
    (net (code "218") (name "unconnected-(USB1-VBUS-PadA9)") (class "Default")
      (node (ref "USB1") (pin "A9") (pinfunction "VBUS_A9") (pintype "passive+no_connect"))
    )
  )
)
